# Radio-86RK-SRAM.net
KiCad netlist of a schematic drawn in EAGLE
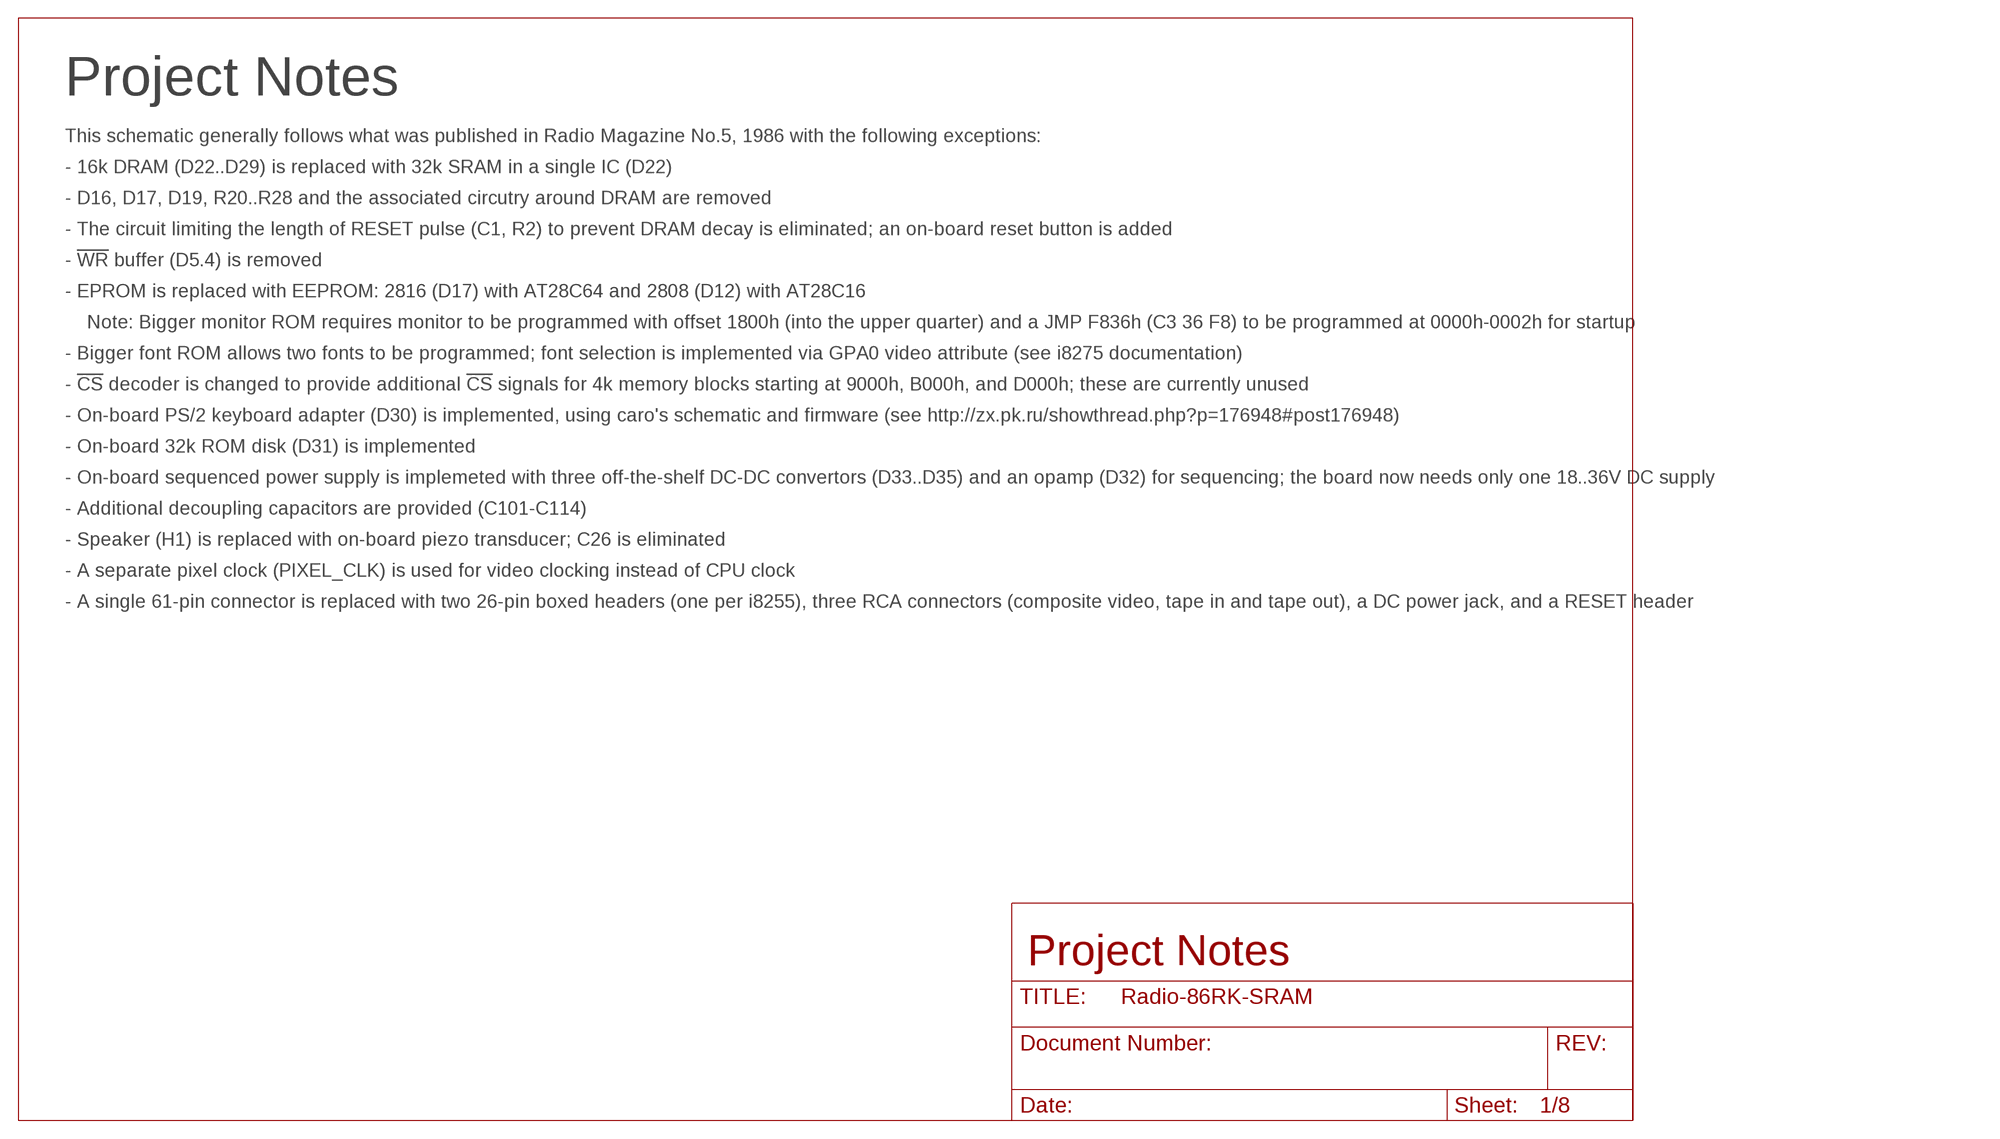
[diagram p0: schematic, sheet 1]
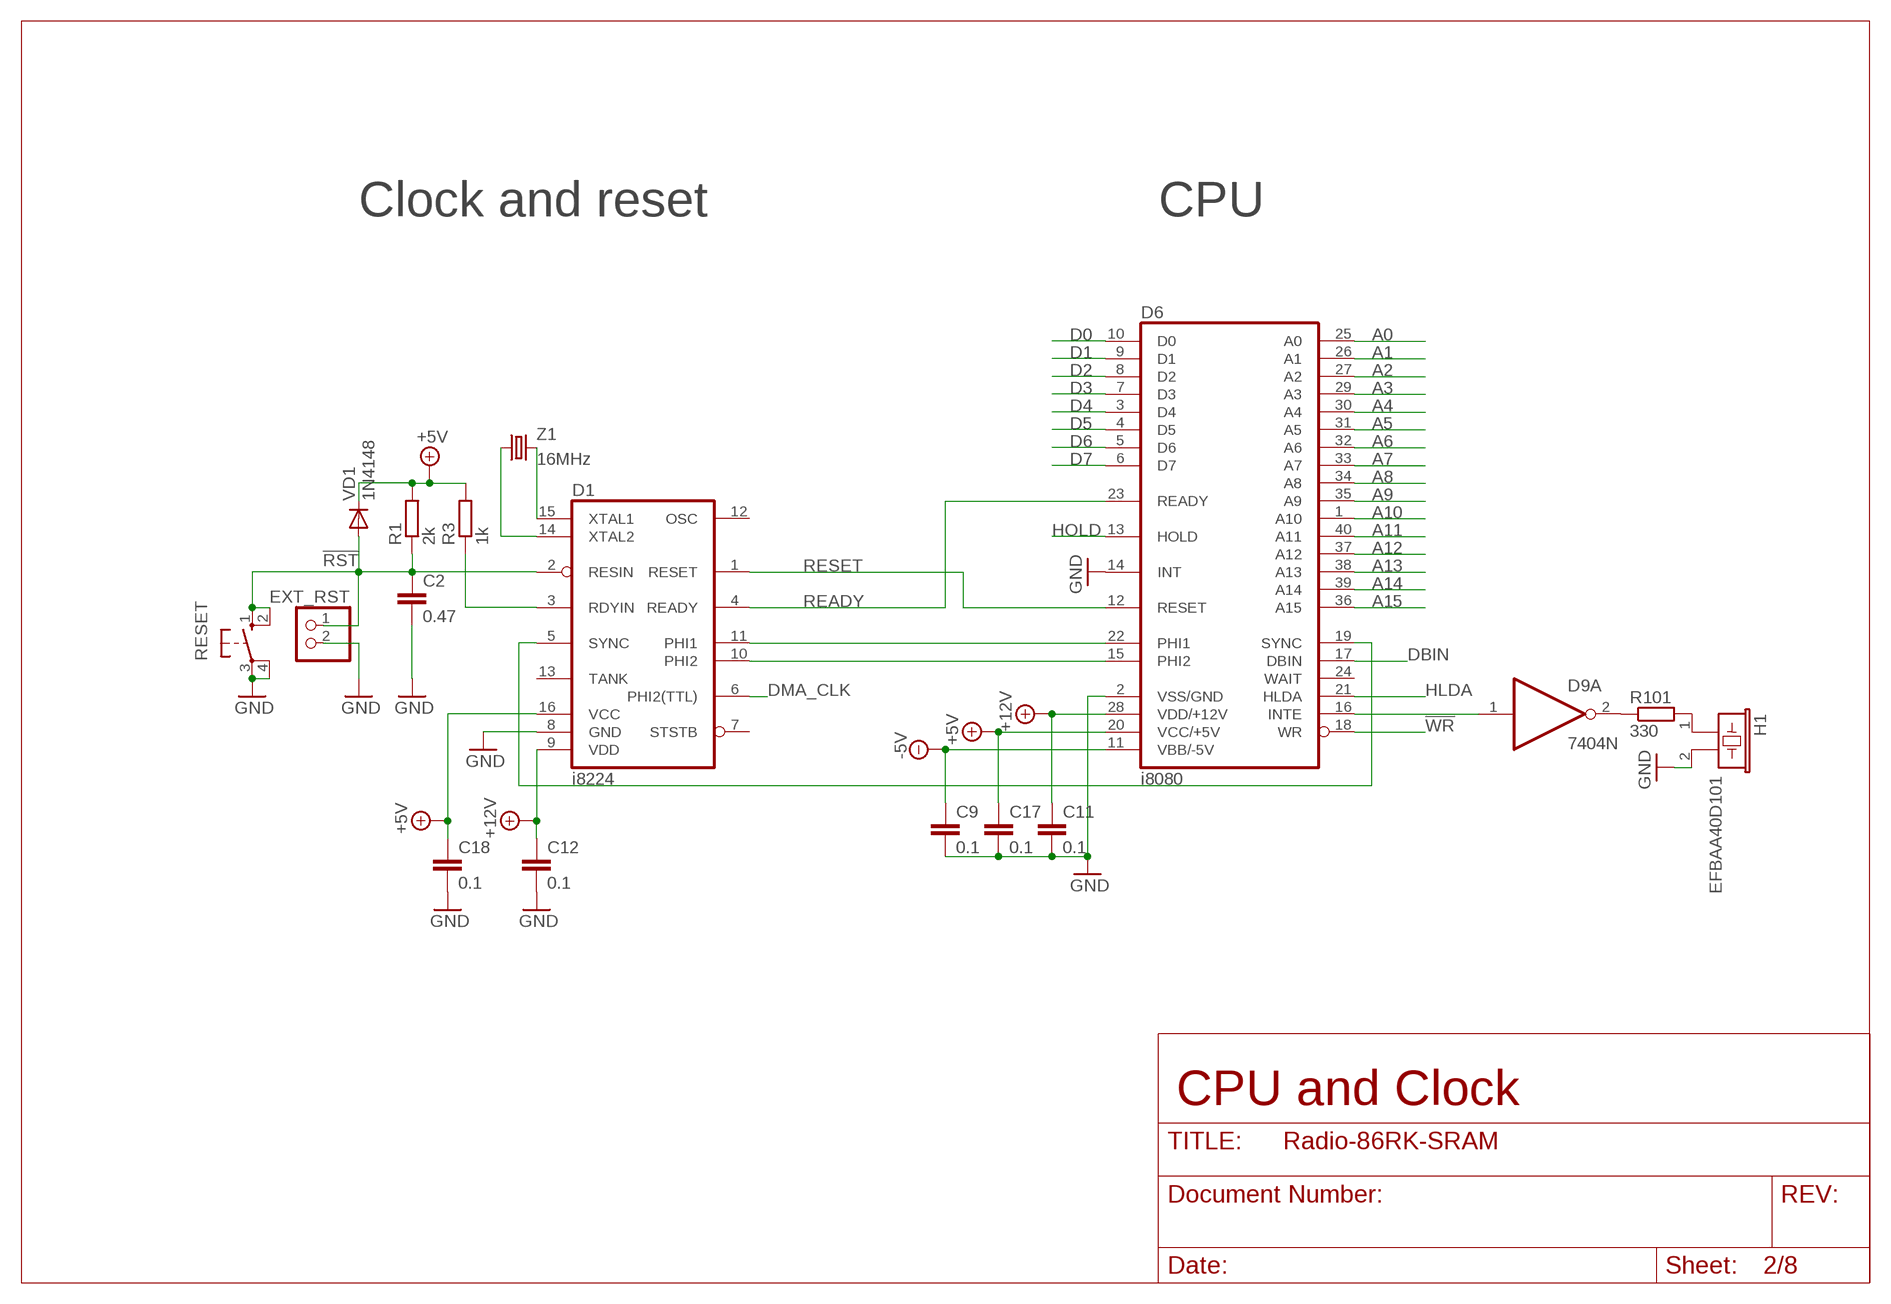
[diagram p1: schematic, sheet 2]
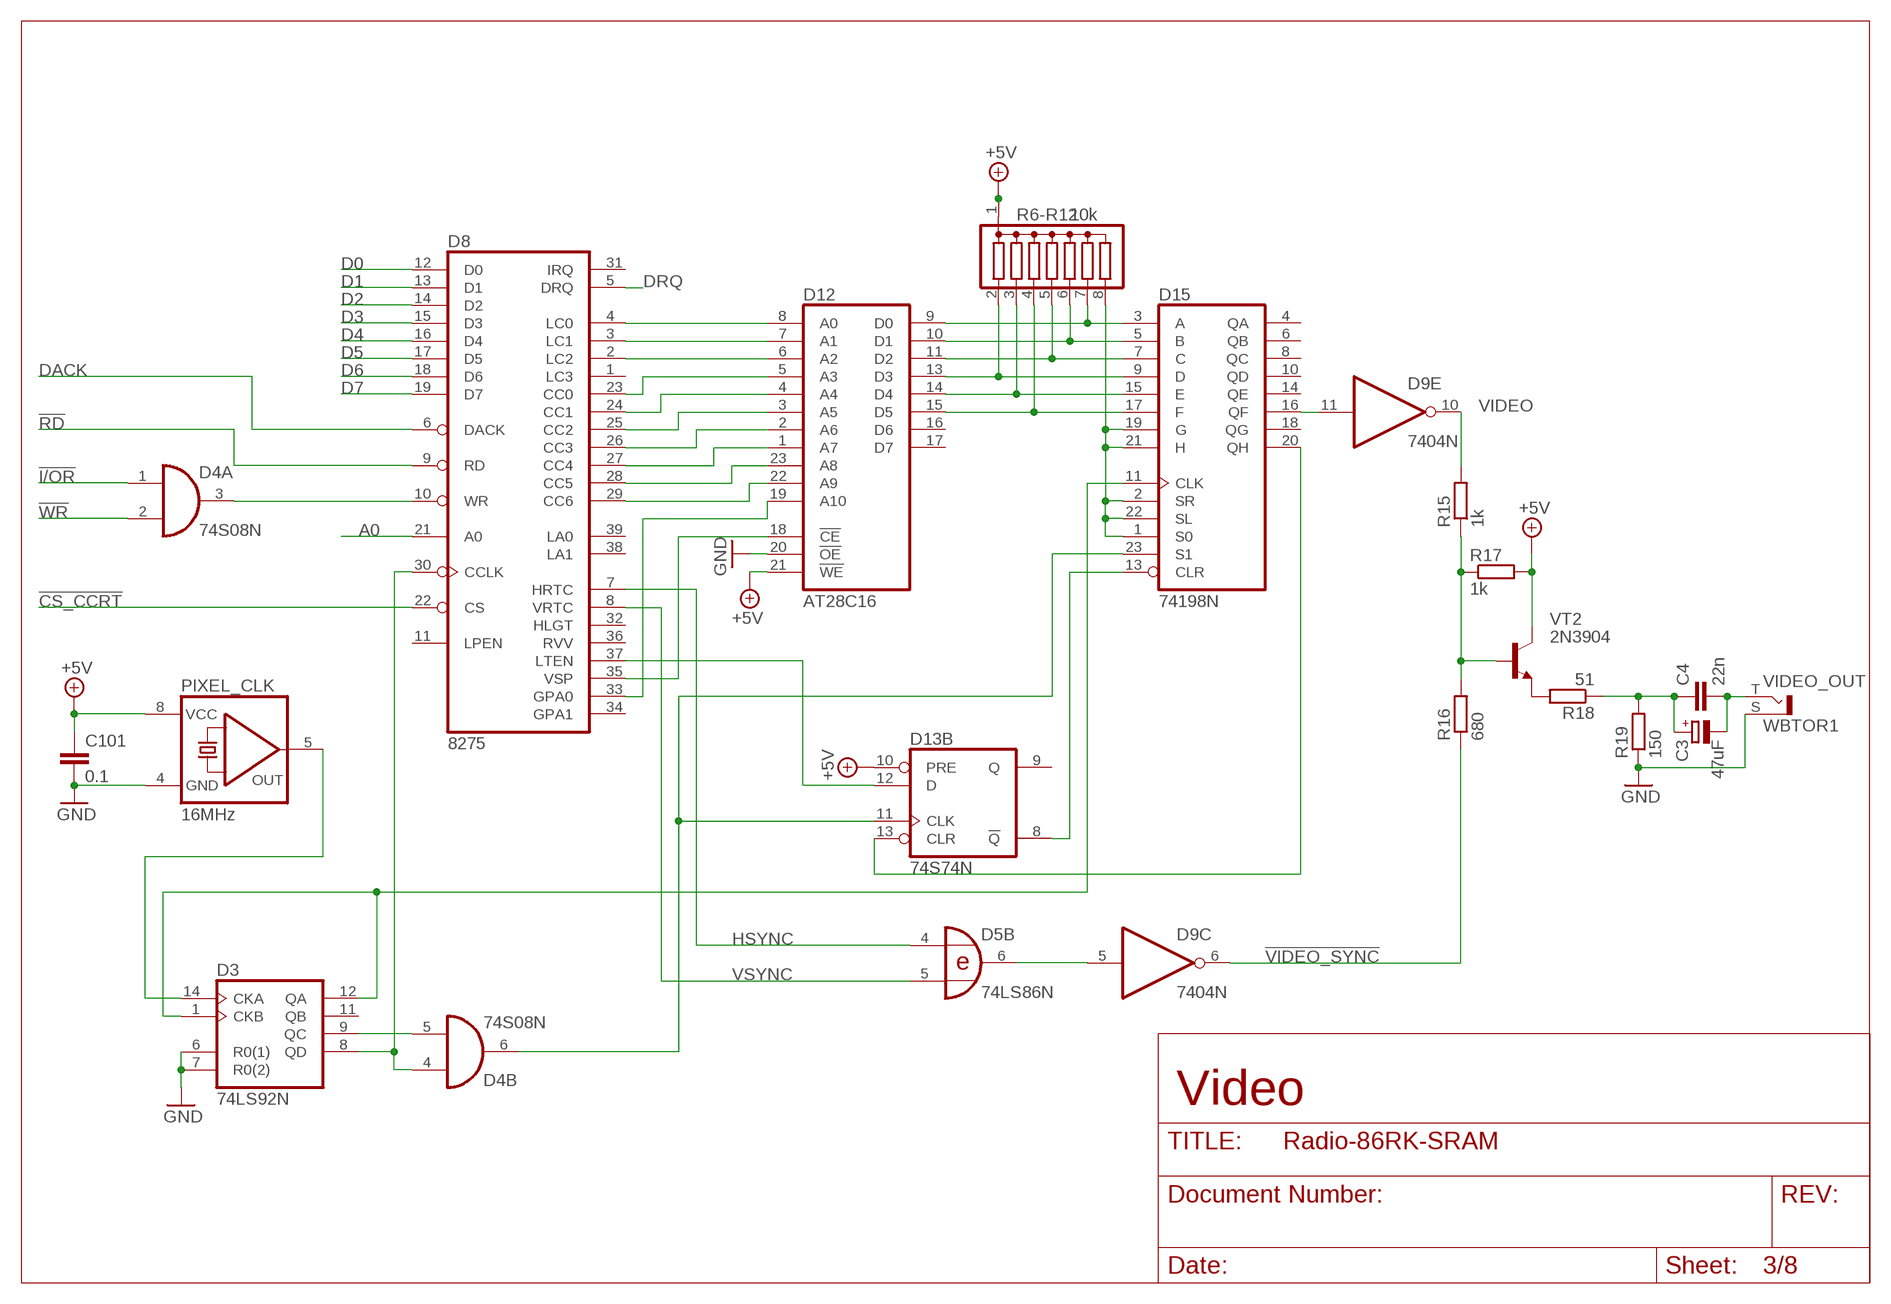
[diagram p2: schematic, sheet 3]
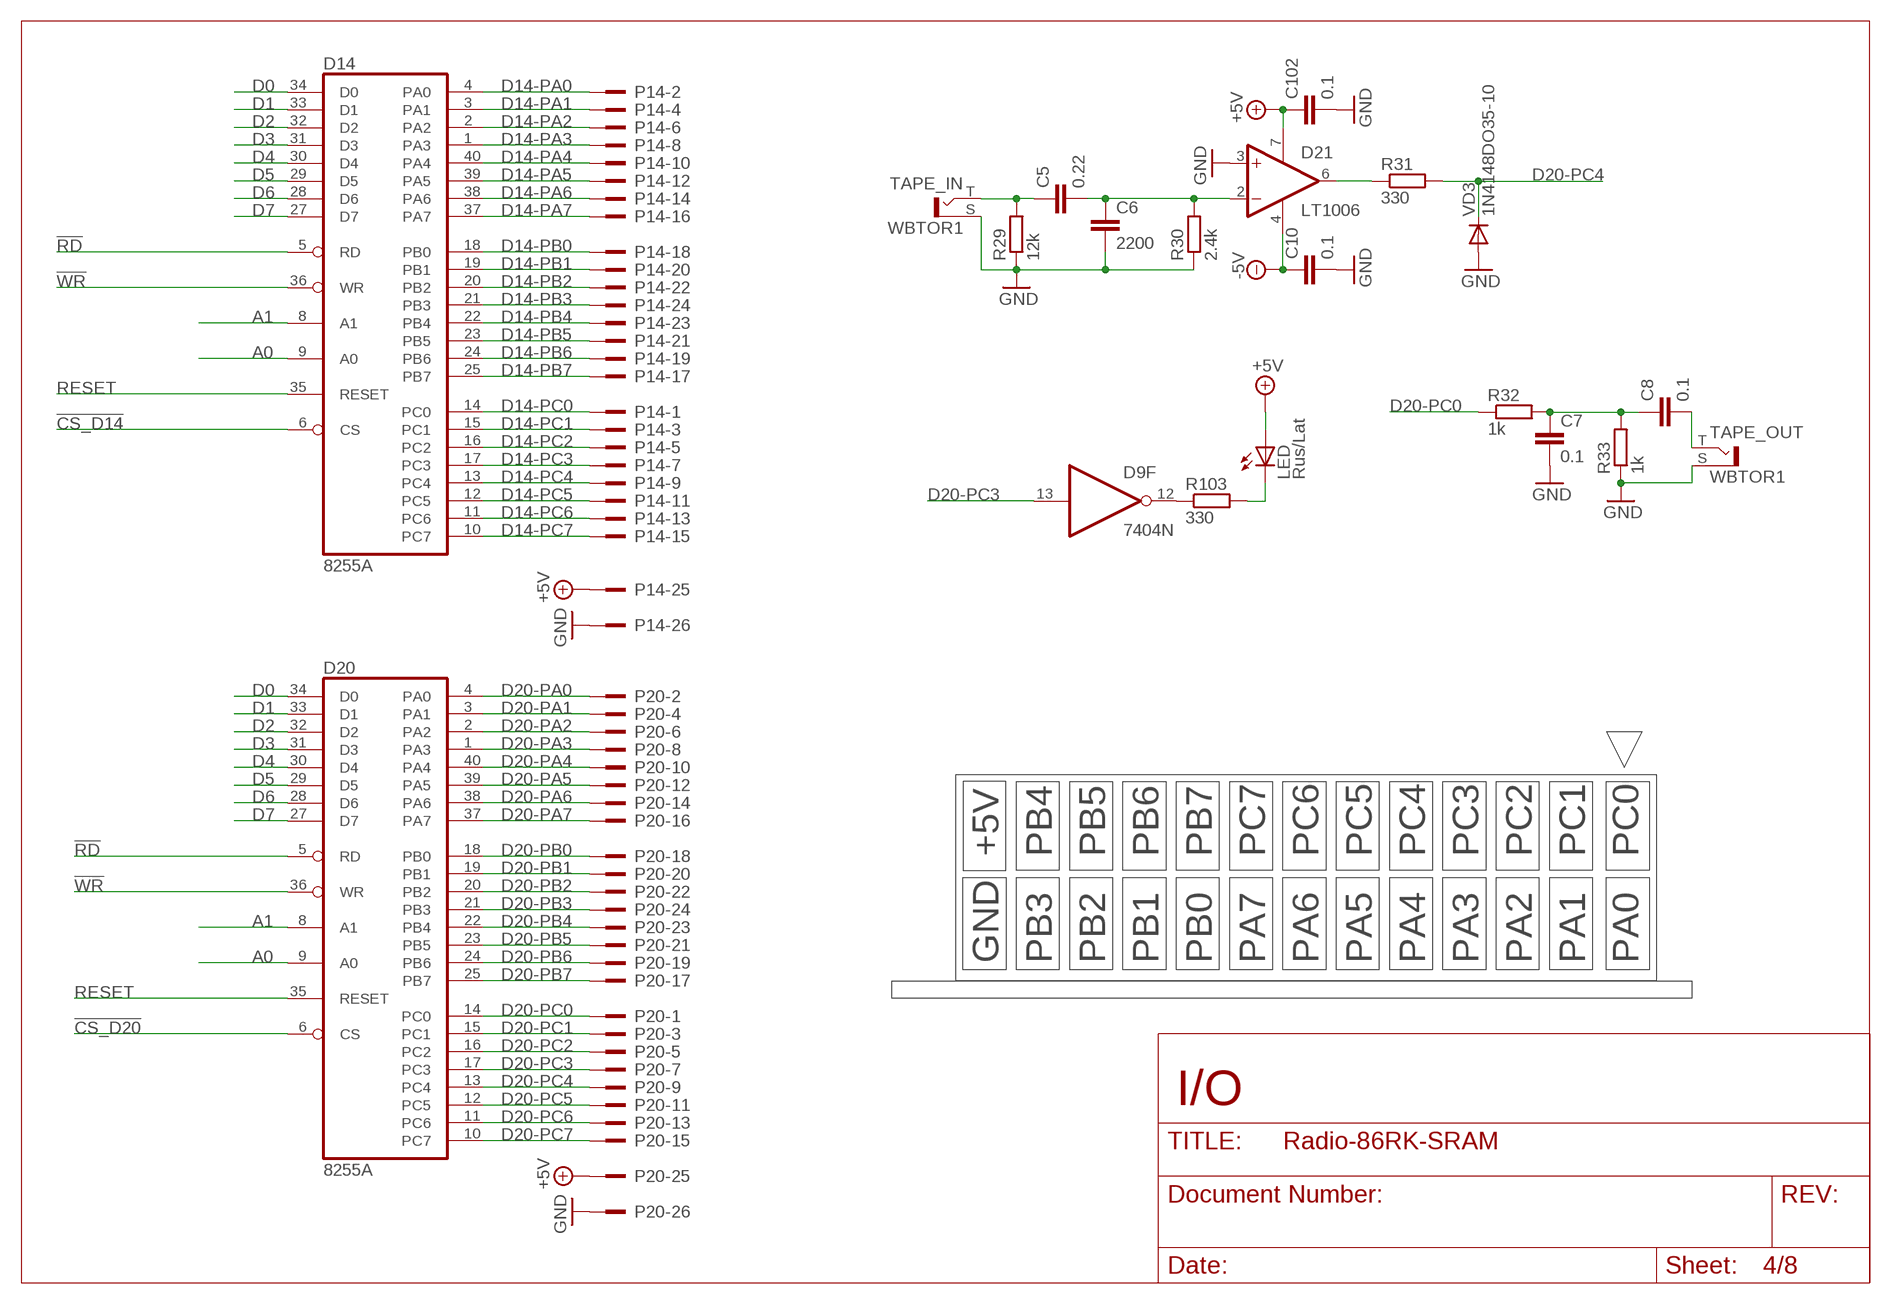
[diagram p3: schematic, sheet 4]
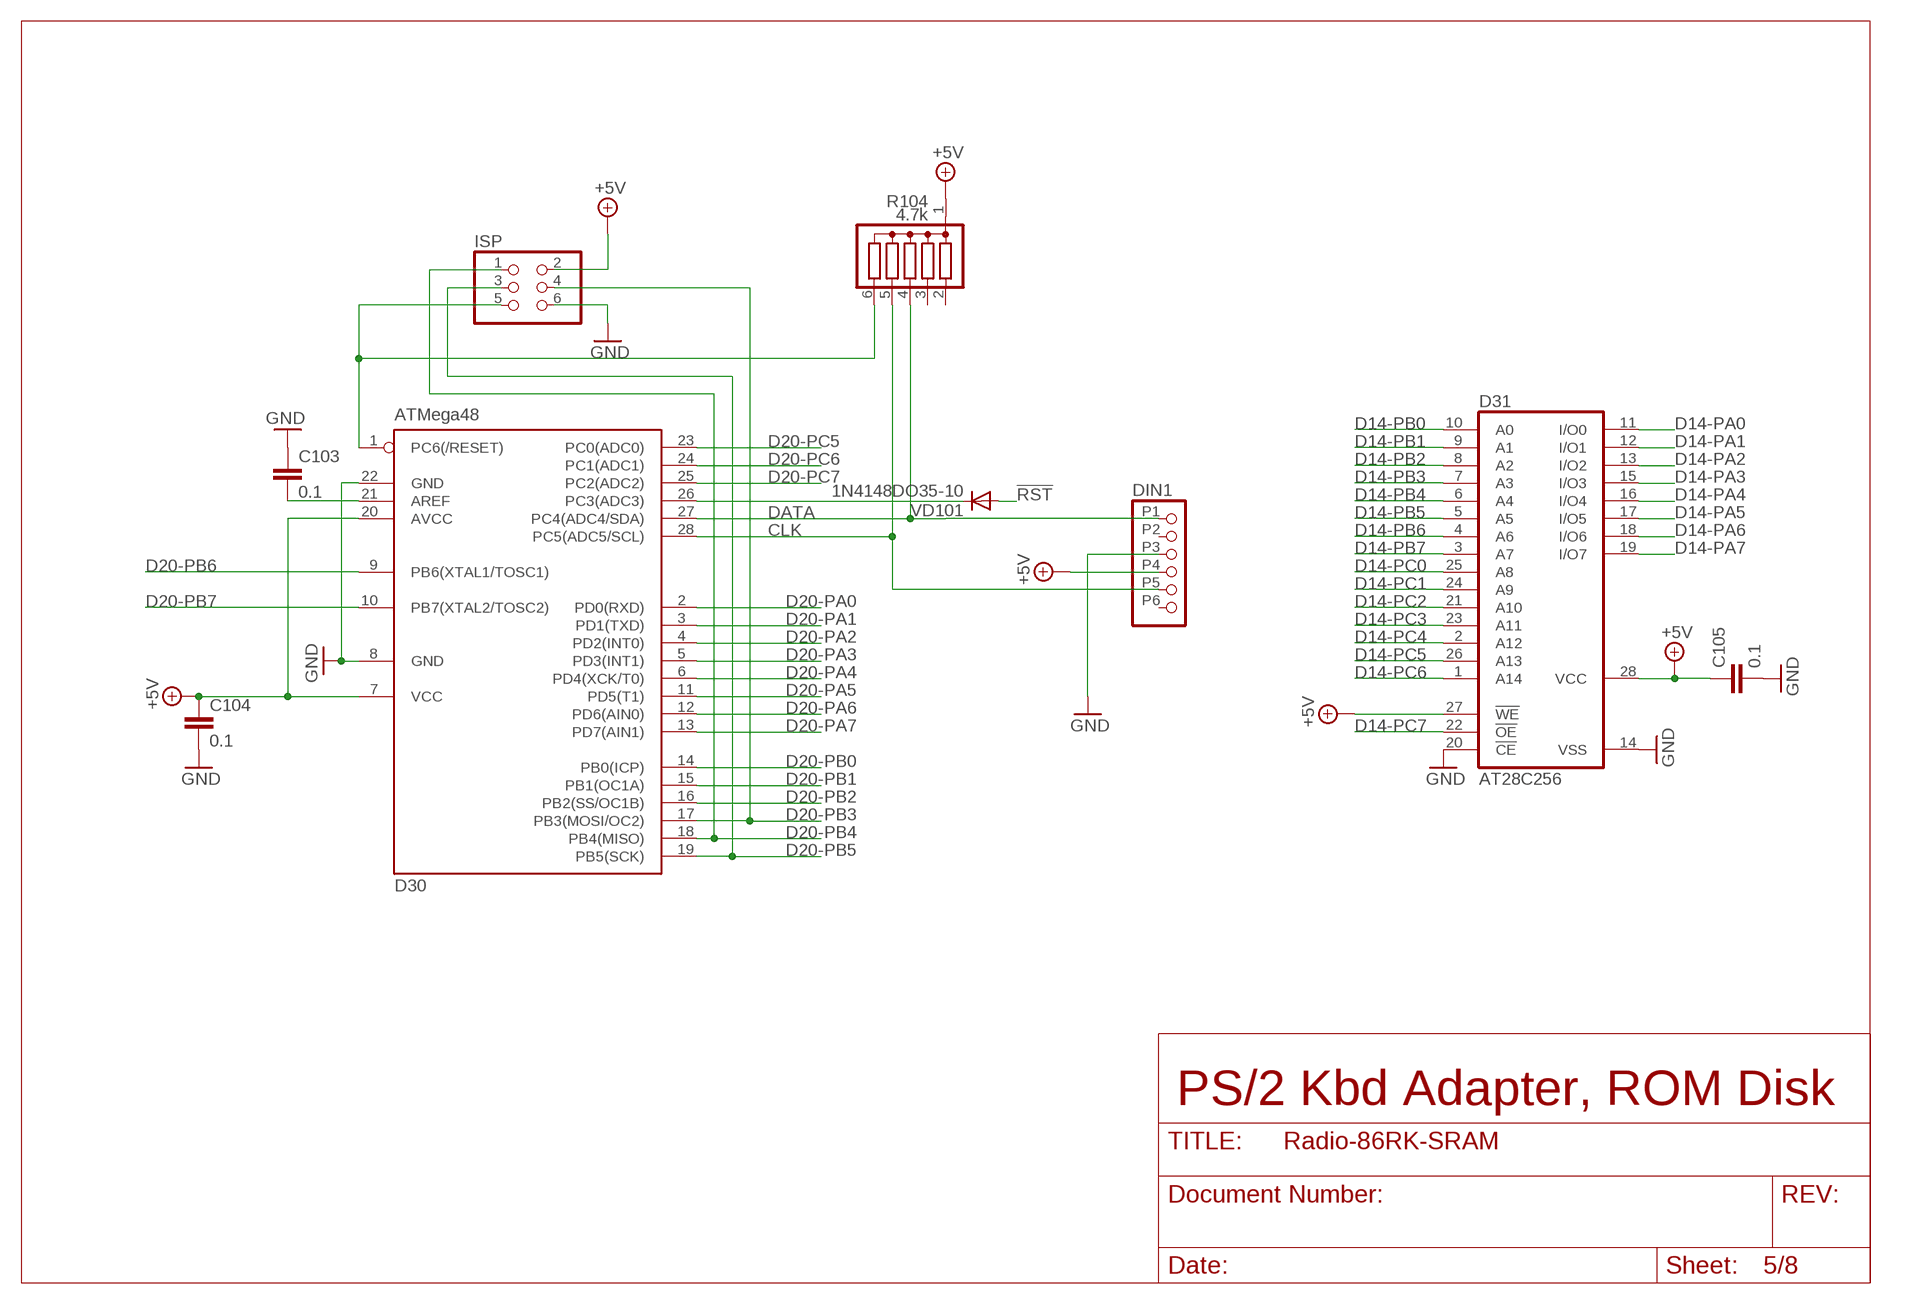
[diagram p4: schematic, sheet 5]
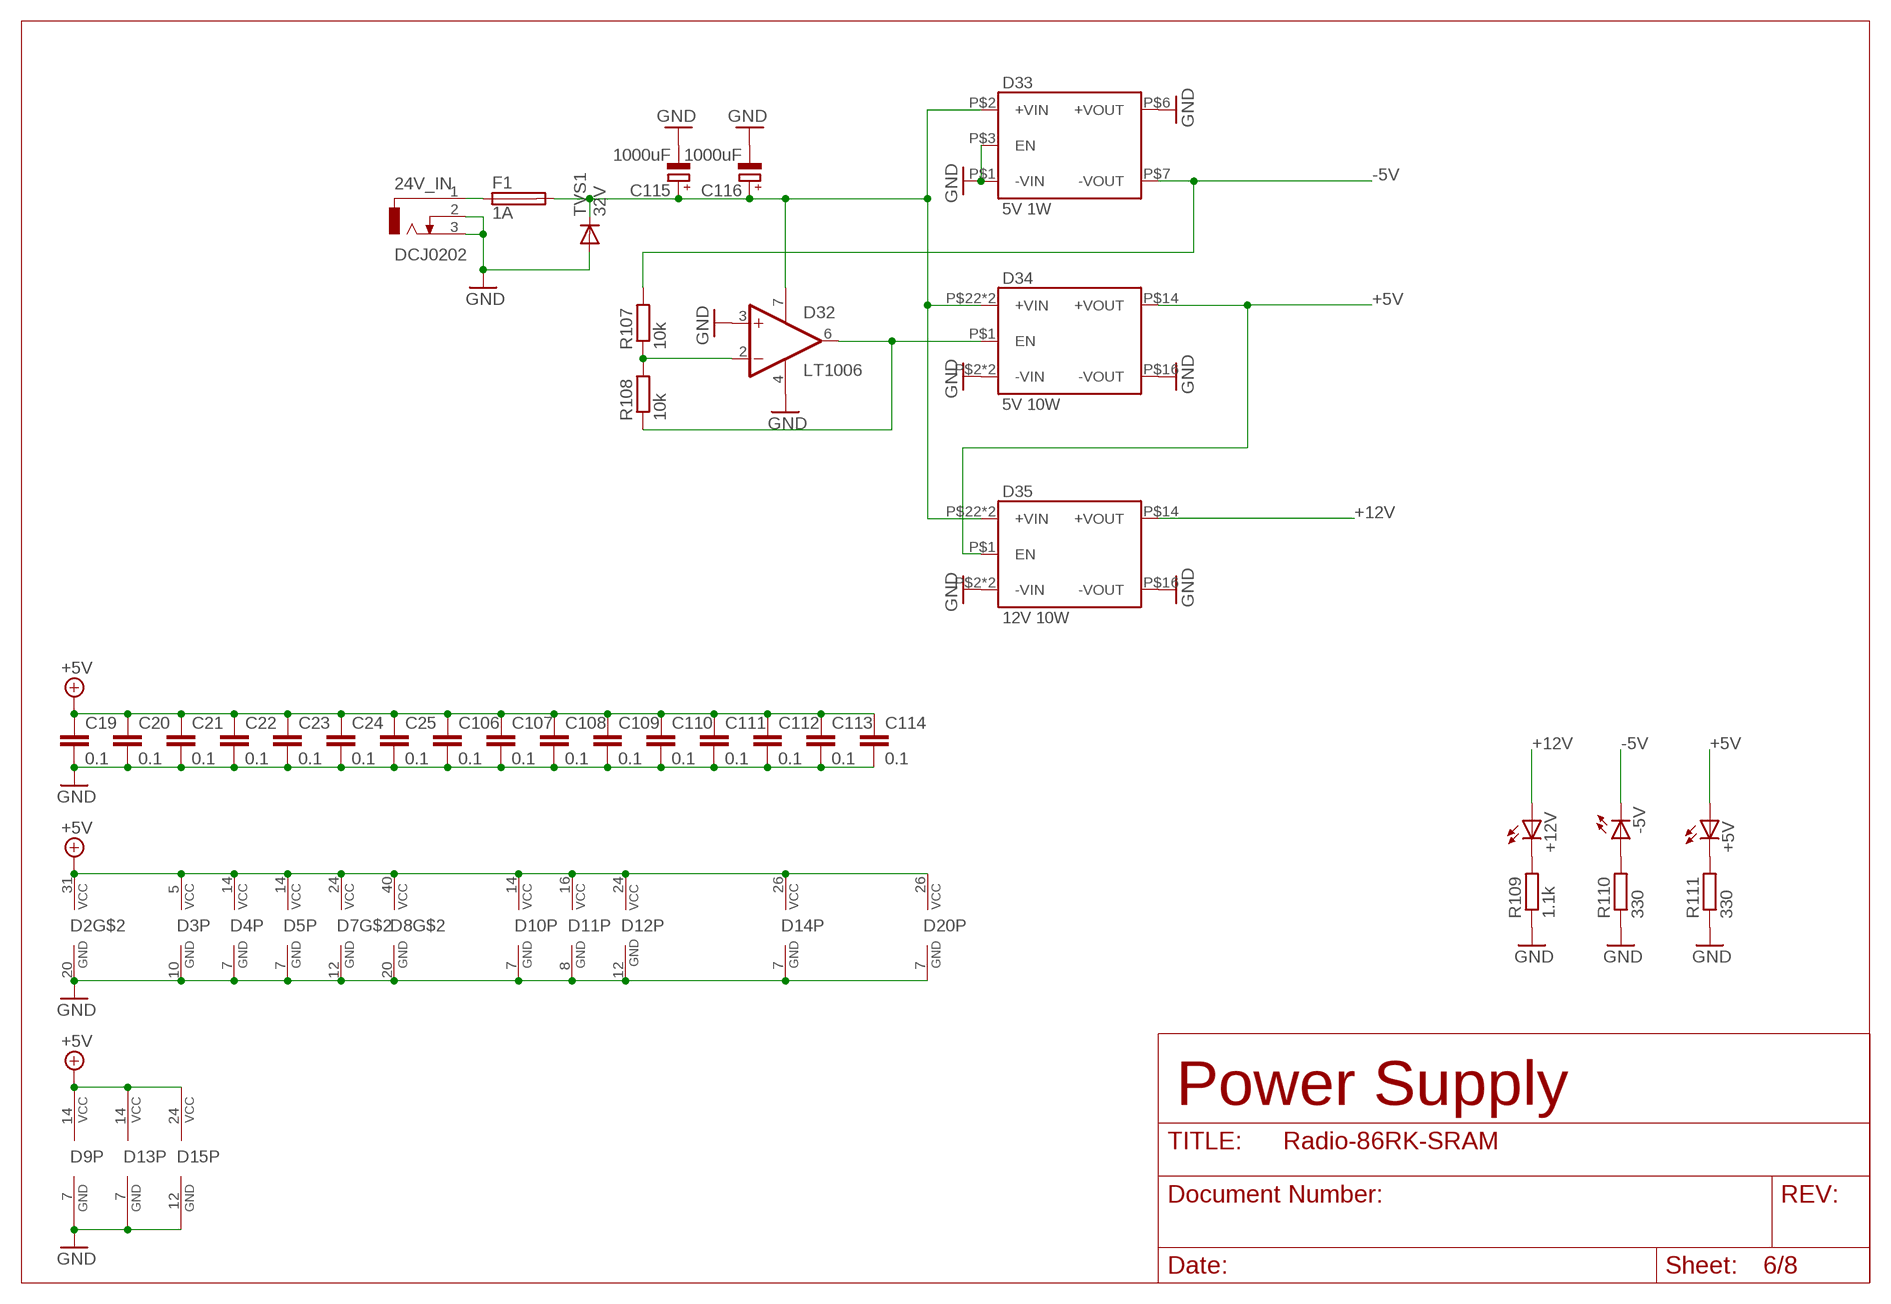
[diagram p5: schematic, sheet 6]
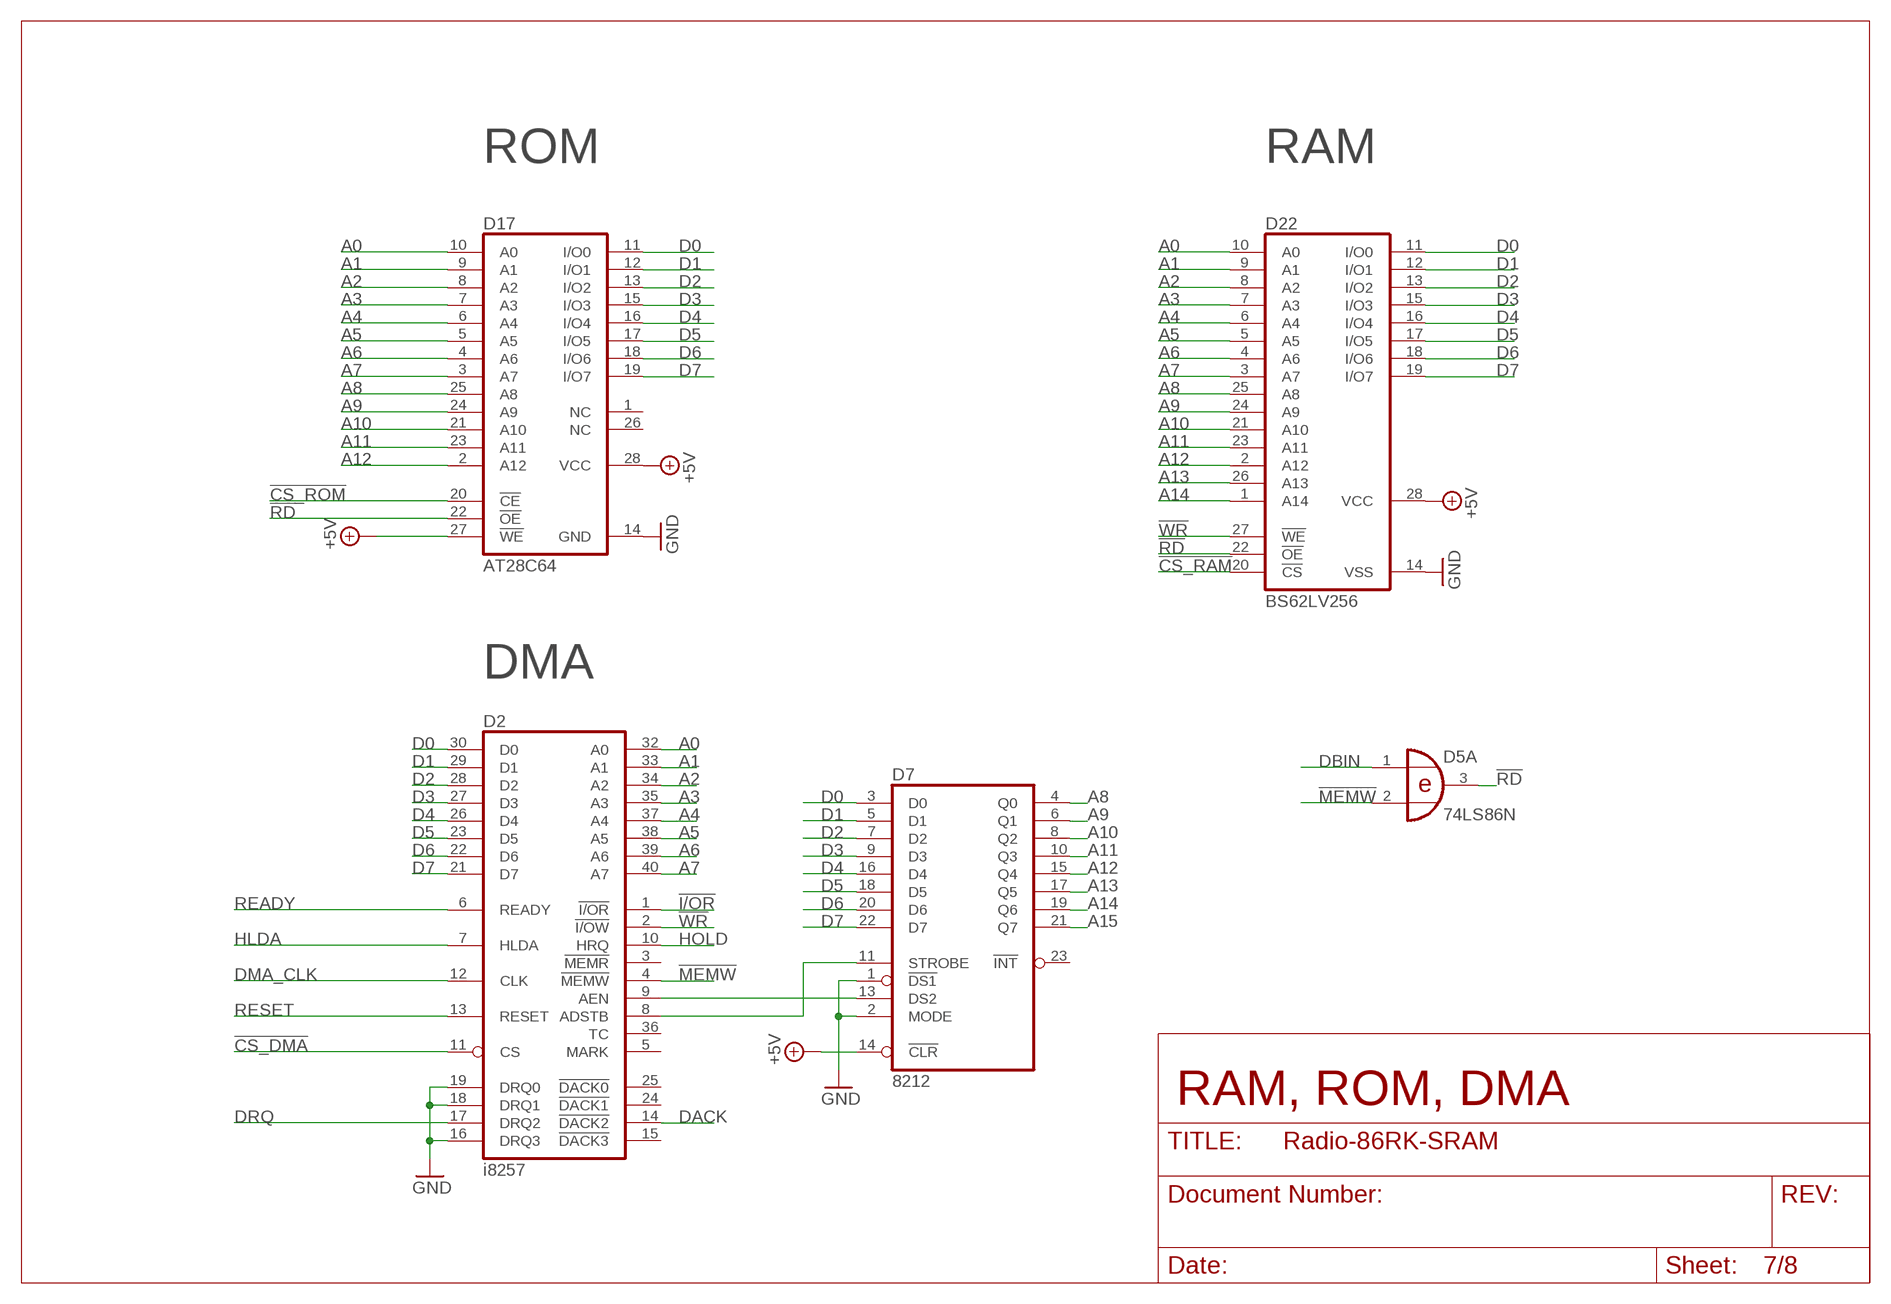
[diagram p6: schematic, sheet 7]
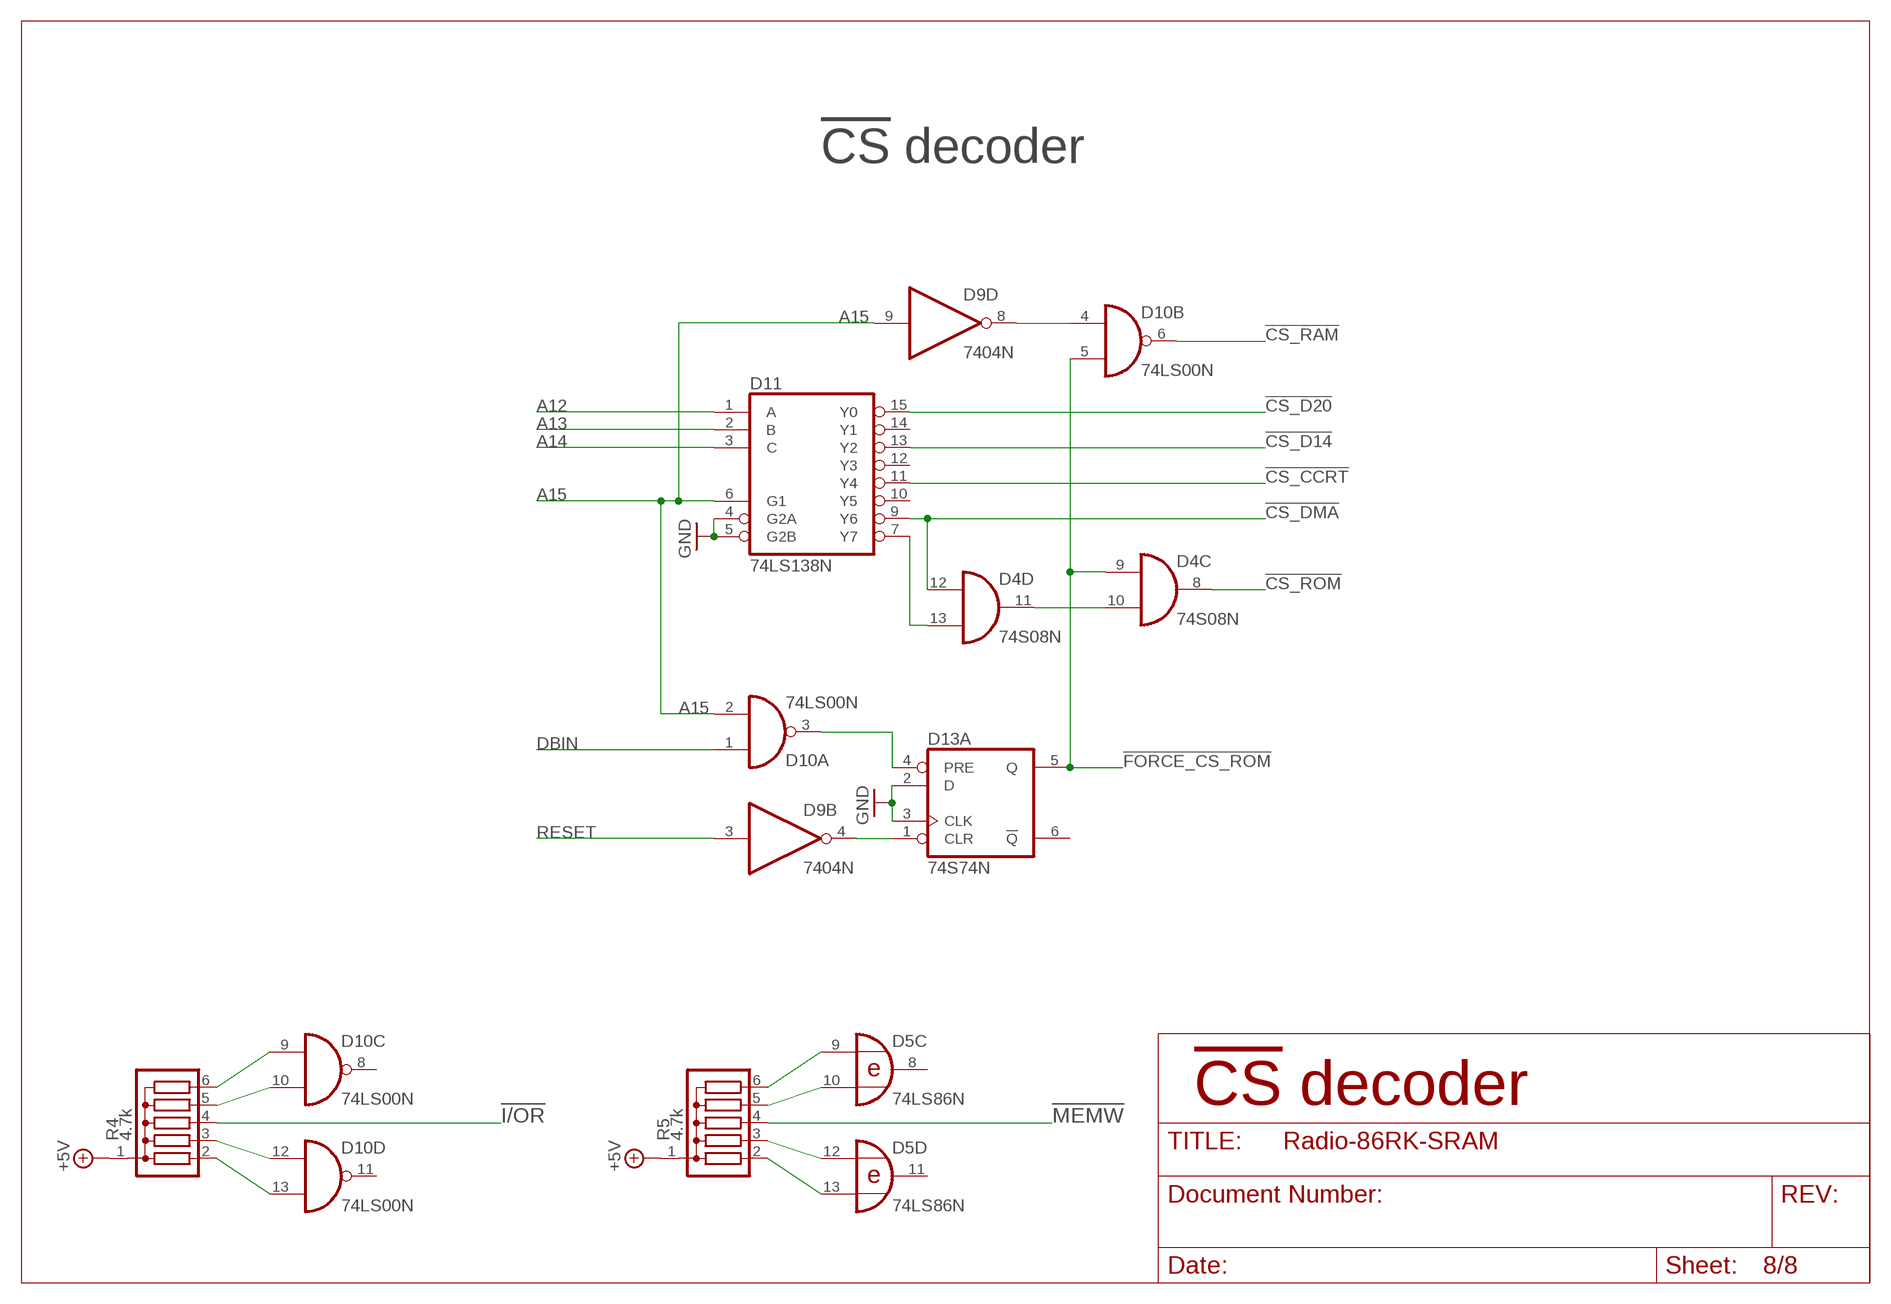
[diagram p7: schematic, sheet 8]

(export (version "E")
  (design (tool "Eeschema 10.0.6"))
  (components
    (comp (ref "C103")
      (value "0.1")
      (footprint "eagle-import:C050-024X044")
      (libsource (lib "eagle-import") (part "C-EU050-024X044"))
    )
    (comp (ref "C104")
      (value "0.1")
      (footprint "eagle-import:C050-024X044")
      (libsource (lib "eagle-import") (part "C-EU050-024X044"))
    )
    (comp (ref "C105")
      (value "0.1")
      (footprint "eagle-import:C050-024X044")
      (libsource (lib "eagle-import") (part "C-EU050-024X044"))
    )
    (comp (ref "D30")
      (value "ATMega48")
      (footprint "eagle-import:DIL28-3")
      (libsource (lib "eagle-import") (part "MEGA8-P"))
    )
    (comp (ref "D31")
      (value "AT28C256")
      (footprint "eagle-import:DIL28-6")
      (fields (field (name "MPN") "HN58C256AP85E"))
      (libsource (lib "eagle-import") (part "58C256P"))
    )
    (comp (ref "DIN1")
      (value "TM0508A/6")
      (footprint "eagle-import:MINI-DIN6")
      (libsource (lib "eagle-import") (part "TM0508A/6"))
    )
    (comp (ref "ISP")
      (value "PINHD-2X3")
      (footprint "eagle-import:2X03")
      (libsource (lib "eagle-import") (part "PINHD-2X3"))
    )
    (comp (ref "R104")
      (value "4.7k")
      (footprint "eagle-import:SIL6")
      (libsource (lib "eagle-import") (part "G05R"))
    )
    (comp (ref "VD101")
      (value "1N4148DO35-10")
      (footprint "eagle-import:DO35-10")
      (libsource (lib "eagle-import") (part "1N4148DO35-10"))
    )
    (comp (ref "D2")
      (value "i8257")
      (footprint "eagle-import:DIL40")
      (libsource (lib "eagle-import") (part "8257"))
    )
    (comp (ref "D5")
      (value "74LS86N")
      (footprint "eagle-import:DIL14")
      (libsource (lib "eagle-import") (part "7486NAC"))
    )
    (comp (ref "D7")
      (value "8212")
      (footprint "eagle-import:DIL24-6")
      (libsource (lib "eagle-import") (part "8212"))
    )
    (comp (ref "D17")
      (value "AT28C64")
      (footprint "eagle-import:DIL28-6")
      (fields (field (name "MPN") "AT28C64B-15PU"))
      (libsource (lib "eagle-import") (part "28C64C"))
    )
    (comp (ref "D22")
      (value "BS62LV256")
      (footprint "eagle-import:DIL28-6")
      (libsource (lib "eagle-import") (part "62256P"))
    )
    (comp (ref "D4")
      (value "74S08N")
      (footprint "eagle-import:DIL14")
      (libsource (lib "eagle-import") (part "7408NS"))
    )
    (comp (ref "D9")
      (value "7404N")
      (footprint "eagle-import:DIL14")
      (libsource (lib "eagle-import") (part "7404N"))
    )
    (comp (ref "D10")
      (value "74LS00N")
      (footprint "eagle-import:DIL14")
      (libsource (lib "eagle-import") (part "7400NHC"))
    )
    (comp (ref "D11")
      (value "74LS138N")
      (footprint "eagle-import:DIL16")
      (libsource (lib "eagle-import") (part "74138NLS"))
    )
    (comp (ref "D13")
      (value "74S74N")
      (footprint "eagle-import:DIL14")
      (libsource (lib "eagle-import") (part "7474NS"))
    )
    (comp (ref "R4")
      (value "4.7k")
      (footprint "eagle-import:SIL6")
      (libsource (lib "eagle-import") (part "G05R"))
    )
    (comp (ref "R5")
      (value "4.7k")
      (footprint "eagle-import:SIL6")
      (libsource (lib "eagle-import") (part "G05R"))
    )
    (comp (ref "+5V")
      (value "LED3MM")
      (footprint "eagle-import:LED3MM")
      (libsource (lib "eagle-import") (part "LED3MM"))
    )
    (comp (ref "+12V")
      (value "LED3MM")
      (footprint "eagle-import:LED3MM")
      (libsource (lib "eagle-import") (part "LED3MM"))
    )
    (comp (ref "-5V")
      (value "LED3MM")
      (footprint "eagle-import:LED3MM")
      (libsource (lib "eagle-import") (part "LED3MM"))
    )
    (comp (ref "24V_IN")
      (value "DCJ0202")
      (footprint "eagle-import:DCJ0202")
      (libsource (lib "eagle-import") (part "DCJ0202"))
    )
    (comp (ref "C19")
      (value "0.1")
      (footprint "eagle-import:C050-024X044")
      (libsource (lib "eagle-import") (part "C-EU050-024X044"))
    )
    (comp (ref "C20")
      (value "0.1")
      (footprint "eagle-import:C050-024X044")
      (libsource (lib "eagle-import") (part "C-EU050-024X044"))
    )
    (comp (ref "C21")
      (value "0.1")
      (footprint "eagle-import:C050-024X044")
      (libsource (lib "eagle-import") (part "C-EU050-024X044"))
    )
    (comp (ref "C22")
      (value "0.1")
      (footprint "eagle-import:C050-024X044")
      (libsource (lib "eagle-import") (part "C-EU050-024X044"))
    )
    (comp (ref "C23")
      (value "0.1")
      (footprint "eagle-import:C050-024X044")
      (libsource (lib "eagle-import") (part "C-EU050-024X044"))
    )
    (comp (ref "C24")
      (value "0.1")
      (footprint "eagle-import:C050-024X044")
      (libsource (lib "eagle-import") (part "C-EU050-024X044"))
    )
    (comp (ref "C25")
      (value "0.1")
      (footprint "eagle-import:C050-024X044")
      (libsource (lib "eagle-import") (part "C-EU050-024X044"))
    )
    (comp (ref "C106")
      (value "0.1")
      (footprint "eagle-import:C050-024X044")
      (libsource (lib "eagle-import") (part "C-EU050-024X044"))
    )
    (comp (ref "C107")
      (value "0.1")
      (footprint "eagle-import:C050-024X044")
      (libsource (lib "eagle-import") (part "C-EU050-024X044"))
    )
    (comp (ref "C108")
      (value "0.1")
      (footprint "eagle-import:C050-024X044")
      (libsource (lib "eagle-import") (part "C-EU050-024X044"))
    )
    (comp (ref "C109")
      (value "0.1")
      (footprint "eagle-import:C050-024X044")
      (libsource (lib "eagle-import") (part "C-EU050-024X044"))
    )
    (comp (ref "C110")
      (value "0.1")
      (footprint "eagle-import:C050-024X044")
      (libsource (lib "eagle-import") (part "C-EU050-024X044"))
    )
    (comp (ref "C111")
      (value "0.1")
      (footprint "eagle-import:C050-024X044")
      (libsource (lib "eagle-import") (part "C-EU050-024X044"))
    )
    (comp (ref "C112")
      (value "0.1")
      (footprint "eagle-import:C050-024X044")
      (libsource (lib "eagle-import") (part "C-EU050-024X044"))
    )
    (comp (ref "C113")
      (value "0.1")
      (footprint "eagle-import:C050-024X044")
      (libsource (lib "eagle-import") (part "C-EU050-024X044"))
    )
    (comp (ref "C114")
      (value "0.1")
      (footprint "eagle-import:C050-024X044")
      (libsource (lib "eagle-import") (part "C-EU050-024X044"))
    )
    (comp (ref "C115")
      (value "1000uF")
      (footprint "eagle-import:E5-13")
      (libsource (lib "eagle-import") (part "CPOL-EUE5-13"))
    )
    (comp (ref "C116")
      (value "1000uF")
      (footprint "eagle-import:E7,5-18")
      (libsource (lib "eagle-import") (part "CPOL-EUE7.5-18"))
    )
    (comp (ref "D3")
      (value "74LS92N")
      (footprint "eagle-import:DIL14")
      (libsource (lib "eagle-import") (part "7492NLS"))
    )
    (comp (ref "D8")
      (value "8275")
      (footprint "eagle-import:DIL40")
      (libsource (lib "eagle-import") (part "8275"))
    )
    (comp (ref "D12")
      (value "AT28C16")
      (footprint "eagle-import:DIL24")
      (libsource (lib "eagle-import") (part "2816"))
    )
    (comp (ref "D14")
      (value "8255A")
      (footprint "eagle-import:DIL40")
      (libsource (lib "eagle-import") (part "8255A"))
    )
    (comp (ref "D15")
      (value "74198N")
      (footprint "eagle-import:DIL24-6")
      (libsource (lib "eagle-import") (part "74198N"))
    )
    (comp (ref "D20")
      (value "8255A")
      (footprint "eagle-import:DIL40")
      (libsource (lib "eagle-import") (part "8255A"))
    )
    (comp (ref "D32")
      (value "LT1006")
      (footprint "eagle-import:DIL08")
      (libsource (lib "eagle-import") (part "1AMP_P7+4N"))
    )
    (comp (ref "D33")
      (value "5V 1W")
      (footprint "eagle-import:DC_DC_SIP")
      (libsource (lib "eagle-import") (part "IW_S"))
    )
    (comp (ref "D34")
      (value "5V 10W")
      (footprint "eagle-import:DC_DC_24PIN")
      (libsource (lib "eagle-import") (part "JTF_S"))
    )
    (comp (ref "D35")
      (value "12V 10W")
      (footprint "eagle-import:DC_DC_24PIN")
      (libsource (lib "eagle-import") (part "JTF_S"))
    )
    (comp (ref "F1")
      (value "1A")
      (footprint "eagle-import:TE5")
      (libsource (lib "eagle-import") (part "TE5"))
    )
    (comp (ref "R107")
      (value "10k")
      (footprint "eagle-import:0207_10")
      (libsource (lib "eagle-import") (part "R-EU_0207/10"))
    )
    (comp (ref "R108")
      (value "10k")
      (footprint "eagle-import:0207_10")
      (libsource (lib "eagle-import") (part "R-EU_0207/10"))
    )
    (comp (ref "R109")
      (value "1.1k")
      (footprint "eagle-import:0207_10")
      (libsource (lib "eagle-import") (part "R-EU_0207/10"))
    )
    (comp (ref "R110")
      (value "330")
      (footprint "eagle-import:0207_10")
      (libsource (lib "eagle-import") (part "R-EU_0207/10"))
    )
    (comp (ref "R111")
      (value "330")
      (footprint "eagle-import:0207_10")
      (libsource (lib "eagle-import") (part "R-EU_0207/10"))
    )
    (comp (ref "TVS1")
      (value "32V")
      (footprint "eagle-import:DO41-10")
      (libsource (lib "eagle-import") (part "DIODE-DO41-10"))
    )
    (comp (ref "C5")
      (value "0.22")
      (footprint "eagle-import:C050-024X044")
      (libsource (lib "eagle-import") (part "C-EU050-024X044"))
    )
    (comp (ref "C6")
      (value "2200")
      (footprint "eagle-import:C050-024X044")
      (libsource (lib "eagle-import") (part "C-EU050-024X044"))
    )
    (comp (ref "C7")
      (value "0.1")
      (footprint "eagle-import:C050-024X044")
      (libsource (lib "eagle-import") (part "C-EU050-024X044"))
    )
    (comp (ref "C8")
      (value "0.1")
      (footprint "eagle-import:C050-024X044")
      (libsource (lib "eagle-import") (part "C-EU050-024X044"))
    )
    (comp (ref "C10")
      (value "0.1")
      (footprint "eagle-import:C050-024X044")
      (libsource (lib "eagle-import") (part "C-EU050-024X044"))
    )
    (comp (ref "C102")
      (value "0.1")
      (footprint "eagle-import:C050-024X044")
      (libsource (lib "eagle-import") (part "C-EU050-024X044"))
    )
    (comp (ref "D21")
      (value "LT1006")
      (footprint "eagle-import:DIL08")
      (libsource (lib "eagle-import") (part "1AMP_P7+4N"))
    )
    (comp (ref "LED")
      (value "Rus/Lat")
      (footprint "eagle-import:LED3MM")
      (libsource (lib "eagle-import") (part "LED3MM"))
    )
    (comp (ref "P14")
      (value "2526-5")
      (footprint "eagle-import:PAK100_2500-5-26")
      (fields (field (name "OC_FARNELL") "9838392"))
      (libsource (lib "eagle-import") (part "2526-5"))
    )
    (comp (ref "P20")
      (value "2526-5")
      (footprint "eagle-import:PAK100_2500-5-26")
      (fields (field (name "OC_FARNELL") "9838392"))
      (libsource (lib "eagle-import") (part "2526-5"))
    )
    (comp (ref "R29")
      (value "12k")
      (footprint "eagle-import:0207_10")
      (libsource (lib "eagle-import") (part "R-EU_0207/10"))
    )
    (comp (ref "R30")
      (value "2.4k")
      (footprint "eagle-import:0207_10")
      (libsource (lib "eagle-import") (part "R-EU_0207/10"))
    )
    (comp (ref "R31")
      (value "330")
      (footprint "eagle-import:0207_10")
      (libsource (lib "eagle-import") (part "R-EU_0207/10"))
    )
    (comp (ref "R32")
      (value "1k")
      (footprint "eagle-import:0207_10")
      (libsource (lib "eagle-import") (part "R-EU_0207/10"))
    )
    (comp (ref "R33")
      (value "1k")
      (footprint "eagle-import:0207_10")
      (libsource (lib "eagle-import") (part "R-EU_0207/10"))
    )
    (comp (ref "R103")
      (value "330")
      (footprint "eagle-import:0207_10")
      (libsource (lib "eagle-import") (part "R-EU_0207/10"))
    )
    (comp (ref "TAPE_IN")
      (value "WBTOR1")
      (footprint "eagle-import:WBTOR1")
      (fields
        (field (name "MPN") "WBTOR 1 BLACK")
        (field (name "MPN_1") "WBTOR 1 BLACK")
        (field (name "OC_FARNELL") "1200146")
        (field (name "OC_NEWARK") "98K2588")
      )
      (libsource (lib "eagle-import") (part "WBTOR1"))
    )
    (comp (ref "TAPE_OUT")
      (value "WBTOR1")
      (footprint "eagle-import:WBTOR1")
      (fields
        (field (name "MPN") "WBTOR 1 BLACK")
        (field (name "MPN_1") "WBTOR 1 BLACK")
        (field (name "OC_FARNELL") "1200146")
        (field (name "OC_NEWARK") "98K2588")
      )
      (libsource (lib "eagle-import") (part "WBTOR1"))
    )
    (comp (ref "VD3")
      (value "1N4148DO35-10")
      (footprint "eagle-import:DO35-10")
      (libsource (lib "eagle-import") (part "1N4148DO35-10"))
    )
    (comp (ref "C3")
      (value "47uF")
      (footprint "eagle-import:E2,5-5")
      (libsource (lib "eagle-import") (part "CPOL-EUE2.5-5"))
    )
    (comp (ref "C4")
      (value "22n")
      (footprint "eagle-import:C050-024X044")
      (libsource (lib "eagle-import") (part "C-EU050-024X044"))
    )
    (comp (ref "C101")
      (value "0.1")
      (footprint "eagle-import:C050-024X044")
      (libsource (lib "eagle-import") (part "C-EU050-024X044"))
    )
    (comp (ref "PIXEL_CLK")
      (value "16MHz")
      (footprint "eagle-import:DIL08S")
      (libsource (lib "eagle-import") (part "QG5460"))
    )
    (comp (ref "R6-R12")
      (value "10k")
      (footprint "eagle-import:SIL8")
      (libsource (lib "eagle-import") (part "G07R"))
    )
    (comp (ref "R15")
      (value "1k")
      (footprint "eagle-import:0207_10")
      (libsource (lib "eagle-import") (part "R-EU_0207/10"))
    )
    (comp (ref "R16")
      (value "680")
      (footprint "eagle-import:0207_10")
      (libsource (lib "eagle-import") (part "R-EU_0207/10"))
    )
    (comp (ref "R17")
      (value "1k")
      (footprint "eagle-import:0207_10")
      (libsource (lib "eagle-import") (part "R-EU_0207/10"))
    )
    (comp (ref "R18")
      (value "51")
      (footprint "eagle-import:0207_10")
      (libsource (lib "eagle-import") (part "R-EU_0207/10"))
    )
    (comp (ref "R19")
      (value "150")
      (footprint "eagle-import:0207_10")
      (libsource (lib "eagle-import") (part "R-EU_0207/10"))
    )
    (comp (ref "VIDEO_OUT")
      (value "WBTOR1")
      (footprint "eagle-import:WBTOR1")
      (fields
        (field (name "MPN") "WBTOR 1 BLACK")
        (field (name "MPN_1") "WBTOR 1 BLACK")
        (field (name "OC_FARNELL") "1200146")
        (field (name "OC_NEWARK") "98K2588")
      )
      (libsource (lib "eagle-import") (part "WBTOR1"))
    )
    (comp (ref "VT2")
      (value "2N3904")
      (footprint "eagle-import:TO92")
      (libsource (lib "eagle-import") (part "2N3904"))
    )
    (comp (ref "C2")
      (value "0.47")
      (footprint "eagle-import:C050-024X044")
      (libsource (lib "eagle-import") (part "C-EU050-024X044"))
    )
    (comp (ref "C9")
      (value "0.1")
      (footprint "eagle-import:C050-024X044")
      (libsource (lib "eagle-import") (part "C-EU050-024X044"))
    )
    (comp (ref "C11")
      (value "0.1")
      (footprint "eagle-import:C050-024X044")
      (libsource (lib "eagle-import") (part "C-EU050-024X044"))
    )
    (comp (ref "C12")
      (value "0.1")
      (footprint "eagle-import:C050-024X044")
      (libsource (lib "eagle-import") (part "C-EU050-024X044"))
    )
    (comp (ref "C17")
      (value "0.1")
      (footprint "eagle-import:C050-024X044")
      (libsource (lib "eagle-import") (part "C-EU050-024X044"))
    )
    (comp (ref "C18")
      (value "0.1")
      (footprint "eagle-import:C050-024X044")
      (libsource (lib "eagle-import") (part "C-EU050-024X044"))
    )
    (comp (ref "D1")
      (value "i8224")
      (footprint "eagle-import:DIL16")
      (libsource (lib "eagle-import") (part "8224"))
    )
    (comp (ref "D6")
      (value "i8080")
      (footprint "eagle-import:DIL40")
      (libsource (lib "eagle-import") (part "8080"))
    )
    (comp (ref "EXT_RST")
      (value "PINHD-1X2")
      (footprint "eagle-import:1X02")
      (libsource (lib "eagle-import") (part "PINHD-1X2"))
    )
    (comp (ref "H1")
      (value "EFBAA40D101")
      (footprint "eagle-import:EFBAA40D101")
      (libsource (lib "eagle-import") (part "EFB?AA40D101"))
    )
    (comp (ref "R1")
      (value "2k")
      (footprint "eagle-import:0207_10")
      (libsource (lib "eagle-import") (part "R-EU_0207/10"))
    )
    (comp (ref "R3")
      (value "1k")
      (footprint "eagle-import:0207_10")
      (libsource (lib "eagle-import") (part "R-EU_0207/10"))
    )
    (comp (ref "R101")
      (value "330")
      (footprint "eagle-import:0207_10")
      (libsource (lib "eagle-import") (part "R-EU_0207/10"))
    )
    (comp (ref "RESET")
      (value "10-XX")
      (footprint "eagle-import:B3F-10XX")
      (fields (field (name "MPN") "B3F-1000"))
      (libsource (lib "eagle-import") (part "10-XX"))
    )
    (comp (ref "VD1")
      (value "1N4148")
      (footprint "eagle-import:DO35-10")
      (libsource (lib "eagle-import") (part "1N4148DO35-10"))
    )
    (comp (ref "Z1")
      (value "16MHz")
      (footprint "eagle-import:HC49U-V")
      (libsource (lib "eagle-import") (part "CRYSTALHC49U-V"))
    )
  )
  (nets
    (net (code "1") (name "+5V") (class "Default")
      (node (ref "+5V") (pin "A") (pinfunction "A_A") (pintype "passive"))
      (node (ref "C101") (pin "1") (pinfunction "1_1") (pintype "passive"))
      (node (ref "C102") (pin "1") (pinfunction "1_1") (pintype "passive"))
      (node (ref "C104") (pin "1") (pinfunction "1_1") (pintype "passive"))
      (node (ref "C105") (pin "1") (pinfunction "1_1") (pintype "passive"))
      (node (ref "C106") (pin "1") (pinfunction "1_1") (pintype "passive"))
      (node (ref "C107") (pin "1") (pinfunction "1_1") (pintype "passive"))
      (node (ref "C108") (pin "1") (pinfunction "1_1") (pintype "passive"))
      (node (ref "C109") (pin "1") (pinfunction "1_1") (pintype "passive"))
      (node (ref "C110") (pin "1") (pinfunction "1_1") (pintype "passive"))
      (node (ref "C111") (pin "1") (pinfunction "1_1") (pintype "passive"))
      (node (ref "C112") (pin "1") (pinfunction "1_1") (pintype "passive"))
      (node (ref "C113") (pin "1") (pinfunction "1_1") (pintype "passive"))
      (node (ref "C114") (pin "1") (pinfunction "1_1") (pintype "passive"))
      (node (ref "C17") (pin "1") (pinfunction "1_1") (pintype "passive"))
      (node (ref "C18") (pin "1") (pinfunction "1_1") (pintype "passive"))
      (node (ref "C19") (pin "1") (pinfunction "1_1") (pintype "passive"))
      (node (ref "C20") (pin "1") (pinfunction "1_1") (pintype "passive"))
      (node (ref "C21") (pin "1") (pinfunction "1_1") (pintype "passive"))
      (node (ref "C22") (pin "1") (pinfunction "1_1") (pintype "passive"))
      (node (ref "C23") (pin "1") (pinfunction "1_1") (pintype "passive"))
      (node (ref "C24") (pin "1") (pinfunction "1_1") (pintype "passive"))
      (node (ref "C25") (pin "1") (pinfunction "1_1") (pintype "passive"))
      (node (ref "D1") (pin "16") (pinfunction "VCC_16") (pintype "power_in"))
      (node (ref "D10") (pin "14") (pinfunction "VCC_14") (pintype "power_in"))
      (node (ref "D11") (pin "16") (pinfunction "VCC_16") (pintype "power_in"))
      (node (ref "D12") (pin "21") (pinfunction "~{WE}_21") (pintype "input"))
      (node (ref "D12") (pin "24") (pinfunction "VCC_24") (pintype "power_in"))
      (node (ref "D13") (pin "10") (pinfunction "PRE_10") (pintype "input"))
      (node (ref "D13") (pin "14") (pinfunction "VCC_14") (pintype "power_in"))
      (node (ref "D14") (pin "26") (pinfunction "VCC_26") (pintype "power_in"))
      (node (ref "D15") (pin "24") (pinfunction "VCC_24") (pintype "power_in"))
      (node (ref "D17") (pin "27") (pinfunction "~{WE}_27") (pintype "input"))
      (node (ref "D17") (pin "28") (pinfunction "VCC_28") (pintype "power_in"))
      (node (ref "D2") (pin "31") (pinfunction "VCC_31") (pintype "power_in"))
      (node (ref "D20") (pin "26") (pinfunction "VCC_26") (pintype "power_in"))
      (node (ref "D21") (pin "7") (pinfunction "V+_7") (pintype "power_in"))
      (node (ref "D22") (pin "28") (pinfunction "VCC_28") (pintype "power_in"))
      (node (ref "D3") (pin "5") (pinfunction "VCC_5") (pintype "power_in"))
      (node (ref "D30") (pin "20") (pinfunction "AVCC_20") (pintype "power_in"))
      (node (ref "D30") (pin "7") (pinfunction "VCC_7") (pintype "power_in"))
      (node (ref "D31") (pin "27") (pinfunction "~{WE}_27") (pintype "input"))
      (node (ref "D31") (pin "28") (pinfunction "VCC_28") (pintype "power_in"))
      (node (ref "D34") (pin "P$14") (pinfunction "+VOUT_P$14") (pintype "passive"))
      (node (ref "D35") (pin "P$1") (pinfunction "EN_P$1") (pintype "input"))
      (node (ref "D4") (pin "14") (pinfunction "VCC_14") (pintype "power_in"))
      (node (ref "D5") (pin "14") (pinfunction "VCC_14") (pintype "power_in"))
      (node (ref "D6") (pin "20") (pinfunction "VCC/+5V_20") (pintype "power_in"))
      (node (ref "D7") (pin "14") (pinfunction "~{CLR}_14") (pintype "input"))
      (node (ref "D7") (pin "24") (pinfunction "VCC_24") (pintype "power_in"))
      (node (ref "D8") (pin "40") (pinfunction "VCC_40") (pintype "power_in"))
      (node (ref "D9") (pin "14") (pinfunction "VCC_14") (pintype "power_in"))
      (node (ref "DIN1") (pin "P4") (pinfunction "4_P4") (pintype "passive"))
      (node (ref "ISP") (pin "2") (pinfunction "2_2") (pintype "passive"))
      (node (ref "LED") (pin "A") (pinfunction "A_A") (pintype "passive"))
      (node (ref "P14") (pin "25") (pinfunction "KL_25") (pintype "passive"))
      (node (ref "P20") (pin "25") (pinfunction "KL_25") (pintype "passive"))
      (node (ref "PIXEL_CLK") (pin "8") (pinfunction "VCC_8") (pintype "power_in"))
      (node (ref "R1") (pin "2") (pinfunction "2_2") (pintype "passive"))
      (node (ref "R104") (pin "1") (pinfunction "1_1") (pintype "passive"))
      (node (ref "R17") (pin "2") (pinfunction "2_2") (pintype "passive"))
      (node (ref "R3") (pin "2") (pinfunction "2_2") (pintype "passive"))
      (node (ref "R4") (pin "1") (pinfunction "1_1") (pintype "passive"))
      (node (ref "R5") (pin "1") (pinfunction "1_1") (pintype "passive"))
      (node (ref "R6-R12") (pin "1") (pinfunction "1_1") (pintype "passive"))
      (node (ref "VD1") (pin "C") (pinfunction "C_C") (pintype "passive"))
      (node (ref "VT2") (pin "1") (pinfunction "C_1") (pintype "passive"))
    )
    (net (code "2") (name "+12V") (class "Default")
      (node (ref "+12V") (pin "A") (pinfunction "A_A") (pintype "passive"))
      (node (ref "C11") (pin "1") (pinfunction "1_1") (pintype "passive"))
      (node (ref "C12") (pin "1") (pinfunction "1_1") (pintype "passive"))
      (node (ref "D1") (pin "9") (pinfunction "VDD_9") (pintype "power_in"))
      (node (ref "D35") (pin "P$14") (pinfunction "+VOUT_P$14") (pintype "passive"))
      (node (ref "D6") (pin "28") (pinfunction "VDD/+12V_28") (pintype "power_in"))
    )
    (net (code "3") (name "-5V") (class "Default")
      (node (ref "-5V") (pin "K") (pinfunction "C_K") (pintype "passive"))
      (node (ref "C10") (pin "1") (pinfunction "1_1") (pintype "passive"))
      (node (ref "C9") (pin "1") (pinfunction "1_1") (pintype "passive"))
      (node (ref "D21") (pin "4") (pinfunction "V-_4") (pintype "power_in"))
      (node (ref "D33") (pin "P$7") (pinfunction "-VOUT_P$7") (pintype "passive"))
      (node (ref "D6") (pin "11") (pinfunction "VBB/-5V_11") (pintype "power_in"))
      (node (ref "R107") (pin "2") (pinfunction "2_2") (pintype "passive"))
    )
    (net (code "4") (name "A0") (class "Default")
      (node (ref "D14") (pin "9") (pinfunction "A0_9") (pintype "input"))
      (node (ref "D17") (pin "10") (pinfunction "A0_10") (pintype "input"))
      (node (ref "D2") (pin "32") (pinfunction "A0_32") (pintype "bidirectional"))
      (node (ref "D20") (pin "9") (pinfunction "A0_9") (pintype "input"))
      (node (ref "D22") (pin "10") (pinfunction "A0_10") (pintype "input"))
      (node (ref "D6") (pin "25") (pinfunction "A0_25") (pintype "output"))
      (node (ref "D8") (pin "21") (pinfunction "A0_21") (pintype "input"))
    )
    (net (code "5") (name "A1") (class "Default")
      (node (ref "D14") (pin "8") (pinfunction "A1_8") (pintype "input"))
      (node (ref "D17") (pin "9") (pinfunction "A1_9") (pintype "input"))
      (node (ref "D2") (pin "33") (pinfunction "A1_33") (pintype "bidirectional"))
      (node (ref "D20") (pin "8") (pinfunction "A1_8") (pintype "input"))
      (node (ref "D22") (pin "9") (pinfunction "A1_9") (pintype "input"))
      (node (ref "D6") (pin "26") (pinfunction "A1_26") (pintype "output"))
    )
    (net (code "6") (name "A2") (class "Default")
      (node (ref "D17") (pin "8") (pinfunction "A2_8") (pintype "input"))
      (node (ref "D2") (pin "34") (pinfunction "A2_34") (pintype "bidirectional"))
      (node (ref "D22") (pin "8") (pinfunction "A2_8") (pintype "input"))
      (node (ref "D6") (pin "27") (pinfunction "A2_27") (pintype "output"))
    )
    (net (code "7") (name "A3") (class "Default")
      (node (ref "D17") (pin "7") (pinfunction "A3_7") (pintype "input"))
      (node (ref "D2") (pin "35") (pinfunction "A3_35") (pintype "bidirectional"))
      (node (ref "D22") (pin "7") (pinfunction "A3_7") (pintype "input"))
      (node (ref "D6") (pin "29") (pinfunction "A3_29") (pintype "output"))
    )
    (net (code "8") (name "A4") (class "Default")
      (node (ref "D17") (pin "6") (pinfunction "A4_6") (pintype "input"))
      (node (ref "D2") (pin "37") (pinfunction "A4_37") (pintype "tri_state"))
      (node (ref "D22") (pin "6") (pinfunction "A4_6") (pintype "input"))
      (node (ref "D6") (pin "30") (pinfunction "A4_30") (pintype "output"))
    )
    (net (code "9") (name "A5") (class "Default")
      (node (ref "D17") (pin "5") (pinfunction "A5_5") (pintype "input"))
      (node (ref "D2") (pin "38") (pinfunction "A5_38") (pintype "tri_state"))
      (node (ref "D22") (pin "5") (pinfunction "A5_5") (pintype "input"))
      (node (ref "D6") (pin "31") (pinfunction "A5_31") (pintype "output"))
    )
    (net (code "10") (name "A6") (class "Default")
      (node (ref "D17") (pin "4") (pinfunction "A6_4") (pintype "input"))
      (node (ref "D2") (pin "39") (pinfunction "A6_39") (pintype "tri_state"))
      (node (ref "D22") (pin "4") (pinfunction "A6_4") (pintype "input"))
      (node (ref "D6") (pin "32") (pinfunction "A6_32") (pintype "output"))
    )
    (net (code "11") (name "A7") (class "Default")
      (node (ref "D17") (pin "3") (pinfunction "A7_3") (pintype "input"))
      (node (ref "D2") (pin "40") (pinfunction "A7_40") (pintype "tri_state"))
      (node (ref "D22") (pin "3") (pinfunction "A7_3") (pintype "input"))
      (node (ref "D6") (pin "33") (pinfunction "A7_33") (pintype "output"))
    )
    (net (code "12") (name "A8") (class "Default")
      (node (ref "D17") (pin "25") (pinfunction "A8_25") (pintype "input"))
      (node (ref "D22") (pin "25") (pinfunction "A8_25") (pintype "input"))
      (node (ref "D6") (pin "34") (pinfunction "A8_34") (pintype "output"))
      (node (ref "D7") (pin "4") (pinfunction "Q0_4") (pintype "bidirectional"))
    )
    (net (code "13") (name "A9") (class "Default")
      (node (ref "D17") (pin "24") (pinfunction "A9_24") (pintype "input"))
      (node (ref "D22") (pin "24") (pinfunction "A9_24") (pintype "input"))
      (node (ref "D6") (pin "35") (pinfunction "A9_35") (pintype "output"))
      (node (ref "D7") (pin "6") (pinfunction "Q1_6") (pintype "bidirectional"))
    )
    (net (code "14") (name "A10") (class "Default")
      (node (ref "D17") (pin "21") (pinfunction "A10_21") (pintype "input"))
      (node (ref "D22") (pin "21") (pinfunction "A10_21") (pintype "input"))
      (node (ref "D6") (pin "1") (pinfunction "A10_1") (pintype "output"))
      (node (ref "D7") (pin "8") (pinfunction "Q2_8") (pintype "bidirectional"))
    )
    (net (code "15") (name "A11") (class "Default")
      (node (ref "D17") (pin "23") (pinfunction "A11_23") (pintype "input"))
      (node (ref "D22") (pin "23") (pinfunction "A11_23") (pintype "input"))
      (node (ref "D6") (pin "40") (pinfunction "A11_40") (pintype "output"))
      (node (ref "D7") (pin "10") (pinfunction "Q3_10") (pintype "bidirectional"))
    )
    (net (code "16") (name "A12") (class "Default")
      (node (ref "D11") (pin "1") (pinfunction "A_1") (pintype "input"))
      (node (ref "D17") (pin "2") (pinfunction "A12_2") (pintype "input"))
      (node (ref "D22") (pin "2") (pinfunction "A12_2") (pintype "input"))
      (node (ref "D6") (pin "37") (pinfunction "A12_37") (pintype "output"))
      (node (ref "D7") (pin "15") (pinfunction "Q4_15") (pintype "bidirectional"))
    )
    (net (code "17") (name "A13") (class "Default")
      (node (ref "D11") (pin "2") (pinfunction "B_2") (pintype "input"))
      (node (ref "D22") (pin "26") (pinfunction "A13_26") (pintype "input"))
      (node (ref "D6") (pin "38") (pinfunction "A13_38") (pintype "output"))
      (node (ref "D7") (pin "17") (pinfunction "Q5_17") (pintype "bidirectional"))
    )
    (net (code "18") (name "A14") (class "Default")
      (node (ref "D11") (pin "3") (pinfunction "C_3") (pintype "input"))
      (node (ref "D22") (pin "1") (pinfunction "A14_1") (pintype "input"))
      (node (ref "D6") (pin "39") (pinfunction "A14_39") (pintype "output"))
      (node (ref "D7") (pin "19") (pinfunction "Q6_19") (pintype "bidirectional"))
    )
    (net (code "19") (name "A15") (class "Default")
      (node (ref "D10") (pin "2") (pinfunction "I1_2") (pintype "input"))
      (node (ref "D11") (pin "6") (pinfunction "G1_6") (pintype "input"))
      (node (ref "D6") (pin "36") (pinfunction "A15_36") (pintype "output"))
      (node (ref "D7") (pin "21") (pinfunction "Q7_21") (pintype "bidirectional"))
      (node (ref "D9") (pin "9") (pinfunction "I_9") (pintype "input"))
    )
    (net (code "20") (name "CLK") (class "Default")
      (node (ref "D30") (pin "28") (pinfunction "PC5(ADC5/SCL)_28") (pintype "bidirectional"))
      (node (ref "DIN1") (pin "P5") (pinfunction "5_P5") (pintype "passive"))
      (node (ref "R104") (pin "5") (pinfunction "5_5") (pintype "passive"))
    )
    (net (code "21") (name "D0") (class "Default")
      (node (ref "D14") (pin "34") (pinfunction "D0_34") (pintype "bidirectional"))
      (node (ref "D17") (pin "11") (pinfunction "I/O0_11") (pintype "bidirectional"))
      (node (ref "D2") (pin "30") (pinfunction "D0_30") (pintype "bidirectional"))
      (node (ref "D20") (pin "34") (pinfunction "D0_34") (pintype "bidirectional"))
      (node (ref "D22") (pin "11") (pinfunction "I/O0_11") (pintype "bidirectional"))
      (node (ref "D6") (pin "10") (pinfunction "D0_10") (pintype "bidirectional"))
      (node (ref "D7") (pin "3") (pinfunction "D0_3") (pintype "bidirectional"))
      (node (ref "D8") (pin "12") (pinfunction "D0_12") (pintype "bidirectional"))
    )
    (net (code "22") (name "D1") (class "Default")
      (node (ref "D14") (pin "33") (pinfunction "D1_33") (pintype "bidirectional"))
      (node (ref "D17") (pin "12") (pinfunction "I/O1_12") (pintype "bidirectional"))
      (node (ref "D2") (pin "29") (pinfunction "D1_29") (pintype "bidirectional"))
      (node (ref "D20") (pin "33") (pinfunction "D1_33") (pintype "bidirectional"))
      (node (ref "D22") (pin "12") (pinfunction "I/O1_12") (pintype "bidirectional"))
      (node (ref "D6") (pin "9") (pinfunction "D1_9") (pintype "bidirectional"))
      (node (ref "D7") (pin "5") (pinfunction "D1_5") (pintype "bidirectional"))
      (node (ref "D8") (pin "13") (pinfunction "D1_13") (pintype "bidirectional"))
    )
    (net (code "23") (name "D2") (class "Default")
      (node (ref "D14") (pin "32") (pinfunction "D2_32") (pintype "bidirectional"))
      (node (ref "D17") (pin "13") (pinfunction "I/O2_13") (pintype "bidirectional"))
      (node (ref "D2") (pin "28") (pinfunction "D2_28") (pintype "bidirectional"))
      (node (ref "D20") (pin "32") (pinfunction "D2_32") (pintype "bidirectional"))
      (node (ref "D22") (pin "13") (pinfunction "I/O2_13") (pintype "bidirectional"))
      (node (ref "D6") (pin "8") (pinfunction "D2_8") (pintype "bidirectional"))
      (node (ref "D7") (pin "7") (pinfunction "D2_7") (pintype "bidirectional"))
      (node (ref "D8") (pin "14") (pinfunction "D2_14") (pintype "bidirectional"))
    )
    (net (code "24") (name "D3") (class "Default")
      (node (ref "D14") (pin "31") (pinfunction "D3_31") (pintype "bidirectional"))
      (node (ref "D17") (pin "15") (pinfunction "I/O3_15") (pintype "bidirectional"))
      (node (ref "D2") (pin "27") (pinfunction "D3_27") (pintype "bidirectional"))
      (node (ref "D20") (pin "31") (pinfunction "D3_31") (pintype "bidirectional"))
      (node (ref "D22") (pin "15") (pinfunction "I/O3_15") (pintype "bidirectional"))
      (node (ref "D6") (pin "7") (pinfunction "D3_7") (pintype "bidirectional"))
      (node (ref "D7") (pin "9") (pinfunction "D3_9") (pintype "bidirectional"))
      (node (ref "D8") (pin "15") (pinfunction "D3_15") (pintype "bidirectional"))
    )
    (net (code "25") (name "D4") (class "Default")
      (node (ref "D14") (pin "30") (pinfunction "D4_30") (pintype "bidirectional"))
      (node (ref "D17") (pin "16") (pinfunction "I/O4_16") (pintype "bidirectional"))
      (node (ref "D2") (pin "26") (pinfunction "D4_26") (pintype "bidirectional"))
      (node (ref "D20") (pin "30") (pinfunction "D4_30") (pintype "bidirectional"))
      (node (ref "D22") (pin "16") (pinfunction "I/O4_16") (pintype "bidirectional"))
      (node (ref "D6") (pin "3") (pinfunction "D4_3") (pintype "bidirectional"))
      (node (ref "D7") (pin "16") (pinfunction "D4_16") (pintype "bidirectional"))
      (node (ref "D8") (pin "16") (pinfunction "D4_16") (pintype "bidirectional"))
    )
    (net (code "26") (name "D5") (class "Default")
      (node (ref "D14") (pin "29") (pinfunction "D5_29") (pintype "bidirectional"))
      (node (ref "D17") (pin "17") (pinfunction "I/O5_17") (pintype "bidirectional"))
      (node (ref "D2") (pin "23") (pinfunction "D5_23") (pintype "bidirectional"))
      (node (ref "D20") (pin "29") (pinfunction "D5_29") (pintype "bidirectional"))
      (node (ref "D22") (pin "17") (pinfunction "I/O5_17") (pintype "bidirectional"))
      (node (ref "D6") (pin "4") (pinfunction "D5_4") (pintype "bidirectional"))
      (node (ref "D7") (pin "18") (pinfunction "D5_18") (pintype "bidirectional"))
      (node (ref "D8") (pin "17") (pinfunction "D5_17") (pintype "bidirectional"))
    )
    (net (code "27") (name "D6") (class "Default")
      (node (ref "D14") (pin "28") (pinfunction "D6_28") (pintype "bidirectional"))
      (node (ref "D17") (pin "18") (pinfunction "I/O6_18") (pintype "bidirectional"))
      (node (ref "D2") (pin "22") (pinfunction "D6_22") (pintype "bidirectional"))
      (node (ref "D20") (pin "28") (pinfunction "D6_28") (pintype "bidirectional"))
      (node (ref "D22") (pin "18") (pinfunction "I/O6_18") (pintype "bidirectional"))
      (node (ref "D6") (pin "5") (pinfunction "D6_5") (pintype "bidirectional"))
      (node (ref "D7") (pin "20") (pinfunction "D6_20") (pintype "bidirectional"))
      (node (ref "D8") (pin "18") (pinfunction "D6_18") (pintype "bidirectional"))
    )
    (net (code "28") (name "D7") (class "Default")
      (node (ref "D14") (pin "27") (pinfunction "D7_27") (pintype "bidirectional"))
      (node (ref "D17") (pin "19") (pinfunction "I/O7_19") (pintype "bidirectional"))
      (node (ref "D2") (pin "21") (pinfunction "D7_21") (pintype "bidirectional"))
      (node (ref "D20") (pin "27") (pinfunction "D7_27") (pintype "bidirectional"))
      (node (ref "D22") (pin "19") (pinfunction "I/O7_19") (pintype "bidirectional"))
      (node (ref "D6") (pin "6") (pinfunction "D7_6") (pintype "bidirectional"))
      (node (ref "D7") (pin "22") (pinfunction "D7_22") (pintype "bidirectional"))
      (node (ref "D8") (pin "19") (pinfunction "D7_19") (pintype "bidirectional"))
    )
    (net (code "29") (name "D14-PA0") (class "Default")
      (node (ref "D14") (pin "4") (pinfunction "PA0_4") (pintype "bidirectional"))
      (node (ref "D31") (pin "11") (pinfunction "I/O0_11") (pintype "tri_state"))
      (node (ref "P14") (pin "2") (pinfunction "KL_2") (pintype "passive"))
    )
    (net (code "30") (name "D14-PA1") (class "Default")
      (node (ref "D14") (pin "3") (pinfunction "PA1_3") (pintype "bidirectional"))
      (node (ref "D31") (pin "12") (pinfunction "I/O1_12") (pintype "tri_state"))
      (node (ref "P14") (pin "4") (pinfunction "KL_4") (pintype "passive"))
    )
    (net (code "31") (name "D14-PA2") (class "Default")
      (node (ref "D14") (pin "2") (pinfunction "PA2_2") (pintype "bidirectional"))
      (node (ref "D31") (pin "13") (pinfunction "I/O2_13") (pintype "tri_state"))
      (node (ref "P14") (pin "6") (pinfunction "KL_6") (pintype "passive"))
    )
    (net (code "32") (name "D14-PA3") (class "Default")
      (node (ref "D14") (pin "1") (pinfunction "PA3_1") (pintype "bidirectional"))
      (node (ref "D31") (pin "15") (pinfunction "I/O3_15") (pintype "tri_state"))
      (node (ref "P14") (pin "8") (pinfunction "KL_8") (pintype "passive"))
    )
    (net (code "33") (name "D14-PA4") (class "Default")
      (node (ref "D14") (pin "40") (pinfunction "PA4_40") (pintype "bidirectional"))
      (node (ref "D31") (pin "16") (pinfunction "I/O4_16") (pintype "tri_state"))
      (node (ref "P14") (pin "10") (pinfunction "KL_10") (pintype "passive"))
    )
    (net (code "34") (name "D14-PA5") (class "Default")
      (node (ref "D14") (pin "39") (pinfunction "PA5_39") (pintype "bidirectional"))
      (node (ref "D31") (pin "17") (pinfunction "I/O5_17") (pintype "tri_state"))
      (node (ref "P14") (pin "12") (pinfunction "KL_12") (pintype "passive"))
    )
    (net (code "35") (name "D14-PA6") (class "Default")
      (node (ref "D14") (pin "38") (pinfunction "PA6_38") (pintype "bidirectional"))
      (node (ref "D31") (pin "18") (pinfunction "I/O6_18") (pintype "tri_state"))
      (node (ref "P14") (pin "14") (pinfunction "KL_14") (pintype "passive"))
    )
    (net (code "36") (name "D14-PA7") (class "Default")
      (node (ref "D14") (pin "37") (pinfunction "PA7_37") (pintype "bidirectional"))
      (node (ref "D31") (pin "19") (pinfunction "I/O7_19") (pintype "tri_state"))
      (node (ref "P14") (pin "16") (pinfunction "KL_16") (pintype "passive"))
    )
    (net (code "37") (name "D14-PB0") (class "Default")
      (node (ref "D14") (pin "18") (pinfunction "PB0_18") (pintype "bidirectional"))
      (node (ref "D31") (pin "10") (pinfunction "A0_10") (pintype "input"))
      (node (ref "P14") (pin "18") (pinfunction "KL_18") (pintype "passive"))
    )
    (net (code "38") (name "D14-PB1") (class "Default")
      (node (ref "D14") (pin "19") (pinfunction "PB1_19") (pintype "bidirectional"))
      (node (ref "D31") (pin "9") (pinfunction "A1_9") (pintype "input"))
      (node (ref "P14") (pin "20") (pinfunction "KL_20") (pintype "passive"))
    )
    (net (code "39") (name "D14-PB2") (class "Default")
      (node (ref "D14") (pin "20") (pinfunction "PB2_20") (pintype "bidirectional"))
      (node (ref "D31") (pin "8") (pinfunction "A2_8") (pintype "input"))
      (node (ref "P14") (pin "22") (pinfunction "KL_22") (pintype "passive"))
    )
    (net (code "40") (name "D14-PB3") (class "Default")
      (node (ref "D14") (pin "21") (pinfunction "PB3_21") (pintype "bidirectional"))
      (node (ref "D31") (pin "7") (pinfunction "A3_7") (pintype "input"))
      (node (ref "P14") (pin "24") (pinfunction "KL_24") (pintype "passive"))
    )
    (net (code "41") (name "D14-PB4") (class "Default")
      (node (ref "D14") (pin "22") (pinfunction "PB4_22") (pintype "bidirectional"))
      (node (ref "D31") (pin "6") (pinfunction "A4_6") (pintype "input"))
      (node (ref "P14") (pin "23") (pinfunction "KL_23") (pintype "passive"))
    )
    (net (code "42") (name "D14-PB5") (class "Default")
      (node (ref "D14") (pin "23") (pinfunction "PB5_23") (pintype "bidirectional"))
      (node (ref "D31") (pin "5") (pinfunction "A5_5") (pintype "input"))
      (node (ref "P14") (pin "21") (pinfunction "KL_21") (pintype "passive"))
    )
    (net (code "43") (name "D14-PB6") (class "Default")
      (node (ref "D14") (pin "24") (pinfunction "PB6_24") (pintype "bidirectional"))
      (node (ref "D31") (pin "4") (pinfunction "A6_4") (pintype "input"))
      (node (ref "P14") (pin "19") (pinfunction "KL_19") (pintype "passive"))
    )
    (net (code "44") (name "D14-PB7") (class "Default")
      (node (ref "D14") (pin "25") (pinfunction "PB7_25") (pintype "bidirectional"))
      (node (ref "D31") (pin "3") (pinfunction "A7_3") (pintype "input"))
      (node (ref "P14") (pin "17") (pinfunction "KL_17") (pintype "passive"))
    )
    (net (code "45") (name "D14-PC0") (class "Default")
      (node (ref "D14") (pin "14") (pinfunction "PC0_14") (pintype "bidirectional"))
      (node (ref "D31") (pin "25") (pinfunction "A8_25") (pintype "input"))
      (node (ref "P14") (pin "1") (pinfunction "KL_1") (pintype "passive"))
    )
    (net (code "46") (name "D14-PC1") (class "Default")
      (node (ref "D14") (pin "15") (pinfunction "PC1_15") (pintype "bidirectional"))
      (node (ref "D31") (pin "24") (pinfunction "A9_24") (pintype "input"))
      (node (ref "P14") (pin "3") (pinfunction "KL_3") (pintype "passive"))
    )
    (net (code "47") (name "D14-PC2") (class "Default")
      (node (ref "D14") (pin "16") (pinfunction "PC2_16") (pintype "bidirectional"))
      (node (ref "D31") (pin "21") (pinfunction "A10_21") (pintype "input"))
      (node (ref "P14") (pin "5") (pinfunction "KL_5") (pintype "passive"))
    )
    (net (code "48") (name "D14-PC3") (class "Default")
      (node (ref "D14") (pin "17") (pinfunction "PC3_17") (pintype "bidirectional"))
      (node (ref "D31") (pin "23") (pinfunction "A11_23") (pintype "input"))
      (node (ref "P14") (pin "7") (pinfunction "KL_7") (pintype "passive"))
    )
    (net (code "49") (name "D14-PC4") (class "Default")
      (node (ref "D14") (pin "13") (pinfunction "PC4_13") (pintype "bidirectional"))
      (node (ref "D31") (pin "2") (pinfunction "A12_2") (pintype "input"))
      (node (ref "P14") (pin "9") (pinfunction "KL_9") (pintype "passive"))
    )
    (net (code "50") (name "D14-PC5") (class "Default")
      (node (ref "D14") (pin "12") (pinfunction "PC5_12") (pintype "bidirectional"))
      (node (ref "D31") (pin "26") (pinfunction "A13_26") (pintype "input"))
      (node (ref "P14") (pin "11") (pinfunction "KL_11") (pintype "passive"))
    )
    (net (code "51") (name "D14-PC6") (class "Default")
      (node (ref "D14") (pin "11") (pinfunction "PC6_11") (pintype "bidirectional"))
      (node (ref "D31") (pin "1") (pinfunction "A14_1") (pintype "input"))
      (node (ref "P14") (pin "13") (pinfunction "KL_13") (pintype "passive"))
    )
    (net (code "52") (name "D14-PC7") (class "Default")
      (node (ref "D14") (pin "10") (pinfunction "PC7_10") (pintype "bidirectional"))
      (node (ref "D31") (pin "22") (pinfunction "~{OE}_22") (pintype "input"))
      (node (ref "P14") (pin "15") (pinfunction "KL_15") (pintype "passive"))
    )
    (net (code "53") (name "D20-PA0") (class "Default")
      (node (ref "D20") (pin "4") (pinfunction "PA0_4") (pintype "bidirectional"))
      (node (ref "D30") (pin "2") (pinfunction "PD0(RXD)_2") (pintype "bidirectional"))
      (node (ref "P20") (pin "2") (pinfunction "KL_2") (pintype "passive"))
    )
    (net (code "54") (name "D20-PA1") (class "Default")
      (node (ref "D20") (pin "3") (pinfunction "PA1_3") (pintype "bidirectional"))
      (node (ref "D30") (pin "3") (pinfunction "PD1(TXD)_3") (pintype "bidirectional"))
      (node (ref "P20") (pin "4") (pinfunction "KL_4") (pintype "passive"))
    )
    (net (code "55") (name "D20-PA2") (class "Default")
      (node (ref "D20") (pin "2") (pinfunction "PA2_2") (pintype "bidirectional"))
      (node (ref "D30") (pin "4") (pinfunction "PD2(INT0)_4") (pintype "bidirectional"))
      (node (ref "P20") (pin "6") (pinfunction "KL_6") (pintype "passive"))
    )
    (net (code "56") (name "D20-PA3") (class "Default")
      (node (ref "D20") (pin "1") (pinfunction "PA3_1") (pintype "bidirectional"))
      (node (ref "D30") (pin "5") (pinfunction "PD3(INT1)_5") (pintype "bidirectional"))
      (node (ref "P20") (pin "8") (pinfunction "KL_8") (pintype "passive"))
    )
    (net (code "57") (name "D20-PA4") (class "Default")
      (node (ref "D20") (pin "40") (pinfunction "PA4_40") (pintype "bidirectional"))
      (node (ref "D30") (pin "6") (pinfunction "PD4(XCK/T0)_6") (pintype "bidirectional"))
      (node (ref "P20") (pin "10") (pinfunction "KL_10") (pintype "passive"))
    )
    (net (code "58") (name "D20-PA5") (class "Default")
      (node (ref "D20") (pin "39") (pinfunction "PA5_39") (pintype "bidirectional"))
      (node (ref "D30") (pin "11") (pinfunction "PD5(T1)_11") (pintype "bidirectional"))
      (node (ref "P20") (pin "12") (pinfunction "KL_12") (pintype "passive"))
    )
    (net (code "59") (name "D20-PA6") (class "Default")
      (node (ref "D20") (pin "38") (pinfunction "PA6_38") (pintype "bidirectional"))
      (node (ref "D30") (pin "12") (pinfunction "PD6(AIN0)_12") (pintype "bidirectional"))
      (node (ref "P20") (pin "14") (pinfunction "KL_14") (pintype "passive"))
    )
    (net (code "60") (name "D20-PA7") (class "Default")
      (node (ref "D20") (pin "37") (pinfunction "PA7_37") (pintype "bidirectional"))
      (node (ref "D30") (pin "13") (pinfunction "PD7(AIN1)_13") (pintype "bidirectional"))
      (node (ref "P20") (pin "16") (pinfunction "KL_16") (pintype "passive"))
    )
    (net (code "61") (name "D20-PB0") (class "Default")
      (node (ref "D20") (pin "18") (pinfunction "PB0_18") (pintype "bidirectional"))
      (node (ref "D30") (pin "14") (pinfunction "PB0(ICP)_14") (pintype "bidirectional"))
      (node (ref "P20") (pin "18") (pinfunction "KL_18") (pintype "passive"))
    )
    (net (code "62") (name "D20-PB1") (class "Default")
      (node (ref "D20") (pin "19") (pinfunction "PB1_19") (pintype "bidirectional"))
      (node (ref "D30") (pin "15") (pinfunction "PB1(OC1A)_15") (pintype "bidirectional"))
      (node (ref "P20") (pin "20") (pinfunction "KL_20") (pintype "passive"))
    )
    (net (code "63") (name "D20-PB2") (class "Default")
      (node (ref "D20") (pin "20") (pinfunction "PB2_20") (pintype "bidirectional"))
      (node (ref "D30") (pin "16") (pinfunction "PB2(SS/OC1B)_16") (pintype "bidirectional"))
      (node (ref "P20") (pin "22") (pinfunction "KL_22") (pintype "passive"))
    )
    (net (code "64") (name "D20-PB3") (class "Default")
      (node (ref "D20") (pin "21") (pinfunction "PB3_21") (pintype "bidirectional"))
      (node (ref "D30") (pin "17") (pinfunction "PB3(MOSI/OC2)_17") (pintype "bidirectional"))
      (node (ref "ISP") (pin "4") (pinfunction "4_4") (pintype "passive"))
      (node (ref "P20") (pin "24") (pinfunction "KL_24") (pintype "passive"))
    )
    (net (code "65") (name "D20-PB4") (class "Default")
      (node (ref "D20") (pin "22") (pinfunction "PB4_22") (pintype "bidirectional"))
      (node (ref "D30") (pin "18") (pinfunction "PB4(MISO)_18") (pintype "bidirectional"))
      (node (ref "ISP") (pin "1") (pinfunction "1_1") (pintype "passive"))
      (node (ref "P20") (pin "23") (pinfunction "KL_23") (pintype "passive"))
    )
    (net (code "66") (name "D20-PB5") (class "Default")
      (node (ref "D20") (pin "23") (pinfunction "PB5_23") (pintype "bidirectional"))
      (node (ref "D30") (pin "19") (pinfunction "PB5(SCK)_19") (pintype "bidirectional"))
      (node (ref "ISP") (pin "3") (pinfunction "3_3") (pintype "passive"))
      (node (ref "P20") (pin "21") (pinfunction "KL_21") (pintype "passive"))
    )
    (net (code "67") (name "D20-PB6") (class "Default")
      (node (ref "D20") (pin "24") (pinfunction "PB6_24") (pintype "bidirectional"))
      (node (ref "D30") (pin "9") (pinfunction "PB6(XTAL1/TOSC1)_9") (pintype "bidirectional"))
      (node (ref "P20") (pin "19") (pinfunction "KL_19") (pintype "passive"))
    )
    (net (code "68") (name "D20-PB7") (class "Default")
      (node (ref "D20") (pin "25") (pinfunction "PB7_25") (pintype "bidirectional"))
      (node (ref "D30") (pin "10") (pinfunction "PB7(XTAL2/TOSC2)_10") (pintype "bidirectional"))
      (node (ref "P20") (pin "17") (pinfunction "KL_17") (pintype "passive"))
    )
    (net (code "69") (name "D20-PC0") (class "Default")
      (node (ref "D20") (pin "14") (pinfunction "PC0_14") (pintype "bidirectional"))
      (node (ref "P20") (pin "1") (pinfunction "KL_1") (pintype "passive"))
      (node (ref "R32") (pin "1") (pinfunction "1_1") (pintype "passive"))
    )
    (net (code "70") (name "D20-PC1") (class "Default")
      (node (ref "D20") (pin "15") (pinfunction "PC1_15") (pintype "bidirectional"))
      (node (ref "P20") (pin "3") (pinfunction "KL_3") (pintype "passive"))
    )
    (net (code "71") (name "D20-PC2") (class "Default")
      (node (ref "D20") (pin "16") (pinfunction "PC2_16") (pintype "bidirectional"))
      (node (ref "P20") (pin "5") (pinfunction "KL_5") (pintype "passive"))
    )
    (net (code "72") (name "D20-PC3") (class "Default")
      (node (ref "D20") (pin "17") (pinfunction "PC3_17") (pintype "bidirectional"))
      (node (ref "D9") (pin "13") (pinfunction "I_13") (pintype "input"))
      (node (ref "P20") (pin "7") (pinfunction "KL_7") (pintype "passive"))
    )
    (net (code "73") (name "D20-PC4") (class "Default")
      (node (ref "D20") (pin "13") (pinfunction "PC4_13") (pintype "bidirectional"))
      (node (ref "P20") (pin "9") (pinfunction "KL_9") (pintype "passive"))
      (node (ref "R31") (pin "2") (pinfunction "2_2") (pintype "passive"))
      (node (ref "VD3") (pin "C") (pinfunction "C_C") (pintype "passive"))
    )
    (net (code "74") (name "D20-PC5") (class "Default")
      (node (ref "D20") (pin "12") (pinfunction "PC5_12") (pintype "bidirectional"))
      (node (ref "D30") (pin "23") (pinfunction "PC0(ADC0)_23") (pintype "bidirectional"))
      (node (ref "P20") (pin "11") (pinfunction "KL_11") (pintype "passive"))
    )
    (net (code "75") (name "D20-PC6") (class "Default")
      (node (ref "D20") (pin "11") (pinfunction "PC6_11") (pintype "bidirectional"))
      (node (ref "D30") (pin "24") (pinfunction "PC1(ADC1)_24") (pintype "bidirectional"))
      (node (ref "P20") (pin "13") (pinfunction "KL_13") (pintype "passive"))
    )
    (net (code "76") (name "D20-PC7") (class "Default")
      (node (ref "D20") (pin "10") (pinfunction "PC7_10") (pintype "bidirectional"))
      (node (ref "D30") (pin "25") (pinfunction "PC2(ADC2)_25") (pintype "bidirectional"))
      (node (ref "P20") (pin "15") (pinfunction "KL_15") (pintype "passive"))
    )
    (net (code "77") (name "DACK") (class "Default")
      (node (ref "D2") (pin "14") (pinfunction "~{DACK2}_14") (pintype "bidirectional"))
      (node (ref "D8") (pin "6") (pinfunction "DACK_6") (pintype "input"))
    )
    (net (code "78") (name "DATA") (class "Default")
      (node (ref "D30") (pin "27") (pinfunction "PC4(ADC4/SDA)_27") (pintype "bidirectional"))
      (node (ref "DIN1") (pin "P1") (pinfunction "1_P1") (pintype "passive"))
      (node (ref "R104") (pin "4") (pinfunction "4_4") (pintype "passive"))
    )
    (net (code "79") (name "DBIN") (class "Default")
      (node (ref "D10") (pin "1") (pinfunction "I0_1") (pintype "input"))
      (node (ref "D5") (pin "1") (pinfunction "I0_1") (pintype "input"))
      (node (ref "D6") (pin "17") (pinfunction "DBIN_17") (pintype "output"))
    )
    (net (code "80") (name "DMA_CLK") (class "Default")
      (node (ref "D1") (pin "6") (pinfunction "PHI2(TTL)_6") (pintype "output"))
      (node (ref "D2") (pin "12") (pinfunction "CLK_12") (pintype "input"))
    )
    (net (code "81") (name "DRQ") (class "Default")
      (node (ref "D2") (pin "17") (pinfunction "DRQ2_17") (pintype "bidirectional"))
      (node (ref "D8") (pin "5") (pinfunction "DRQ_5") (pintype "bidirectional"))
    )
    (net (code "82") (name "GND") (class "Default")
      (node (ref "24V_IN") (pin "2") (pinfunction "2_2") (pintype "passive"))
      (node (ref "24V_IN") (pin "3") (pinfunction "3_3") (pintype "passive"))
      (node (ref "C10") (pin "2") (pinfunction "2_2") (pintype "passive"))
      (node (ref "C101") (pin "2") (pinfunction "2_2") (pintype "passive"))
      (node (ref "C102") (pin "2") (pinfunction "2_2") (pintype "passive"))
      (node (ref "C103") (pin "1") (pinfunction "1_1") (pintype "passive"))
      (node (ref "C104") (pin "2") (pinfunction "2_2") (pintype "passive"))
      (node (ref "C105") (pin "2") (pinfunction "2_2") (pintype "passive"))
      (node (ref "C106") (pin "2") (pinfunction "2_2") (pintype "passive"))
      (node (ref "C107") (pin "2") (pinfunction "2_2") (pintype "passive"))
      (node (ref "C108") (pin "2") (pinfunction "2_2") (pintype "passive"))
      (node (ref "C109") (pin "2") (pinfunction "2_2") (pintype "passive"))
      (node (ref "C11") (pin "2") (pinfunction "2_2") (pintype "passive"))
      (node (ref "C110") (pin "2") (pinfunction "2_2") (pintype "passive"))
      (node (ref "C111") (pin "2") (pinfunction "2_2") (pintype "passive"))
      (node (ref "C112") (pin "2") (pinfunction "2_2") (pintype "passive"))
      (node (ref "C113") (pin "2") (pinfunction "2_2") (pintype "passive"))
      (node (ref "C114") (pin "2") (pinfunction "2_2") (pintype "passive"))
      (node (ref "C115") (pin "-") (pinfunction "-_-") (pintype "passive"))
      (node (ref "C116") (pin "-") (pinfunction "-_-") (pintype "passive"))
      (node (ref "C12") (pin "2") (pinfunction "2_2") (pintype "passive"))
      (node (ref "C17") (pin "2") (pinfunction "2_2") (pintype "passive"))
      (node (ref "C18") (pin "2") (pinfunction "2_2") (pintype "passive"))
      (node (ref "C19") (pin "2") (pinfunction "2_2") (pintype "passive"))
      (node (ref "C2") (pin "2") (pinfunction "2_2") (pintype "passive"))
      (node (ref "C20") (pin "2") (pinfunction "2_2") (pintype "passive"))
      (node (ref "C21") (pin "2") (pinfunction "2_2") (pintype "passive"))
      (node (ref "C22") (pin "2") (pinfunction "2_2") (pintype "passive"))
      (node (ref "C23") (pin "2") (pinfunction "2_2") (pintype "passive"))
      (node (ref "C24") (pin "2") (pinfunction "2_2") (pintype "passive"))
      (node (ref "C25") (pin "2") (pinfunction "2_2") (pintype "passive"))
      (node (ref "C6") (pin "2") (pinfunction "2_2") (pintype "passive"))
      (node (ref "C7") (pin "2") (pinfunction "2_2") (pintype "passive"))
      (node (ref "C9") (pin "2") (pinfunction "2_2") (pintype "passive"))
      (node (ref "D1") (pin "8") (pinfunction "GND_8") (pintype "power_in"))
      (node (ref "D10") (pin "7") (pinfunction "GND_7") (pintype "power_in"))
      (node (ref "D11") (pin "4") (pinfunction "G2A_4") (pintype "input"))
      (node (ref "D11") (pin "5") (pinfunction "G2B_5") (pintype "input"))
      (node (ref "D11") (pin "8") (pinfunction "GND_8") (pintype "power_in"))
      (node (ref "D12") (pin "12") (pinfunction "GND_12") (pintype "power_in"))
      (node (ref "D12") (pin "20") (pinfunction "~{OE}_20") (pintype "input"))
      (node (ref "D13") (pin "2") (pinfunction "D_2") (pintype "input"))
      (node (ref "D13") (pin "3") (pinfunction "CLK_3") (pintype "input"))
      (node (ref "D13") (pin "7") (pinfunction "GND_7") (pintype "power_in"))
      (node (ref "D14") (pin "7") (pinfunction "GND_7") (pintype "power_in"))
      (node (ref "D15") (pin "12") (pinfunction "GND_12") (pintype "power_in"))
      (node (ref "D17") (pin "14") (pinfunction "GND_14") (pintype "power_in"))
      (node (ref "D2") (pin "16") (pinfunction "DRQ3_16") (pintype "bidirectional"))
      (node (ref "D2") (pin "18") (pinfunction "DRQ1_18") (pintype "bidirectional"))
      (node (ref "D2") (pin "19") (pinfunction "DRQ0_19") (pintype "bidirectional"))
      (node (ref "D2") (pin "20") (pinfunction "GND_20") (pintype "power_in"))
      (node (ref "D20") (pin "7") (pinfunction "GND_7") (pintype "power_in"))
      (node (ref "D21") (pin "3") (pinfunction "+IN_3") (pintype "input"))
      (node (ref "D22") (pin "14") (pinfunction "VSS_14") (pintype "power_in"))
      (node (ref "D3") (pin "10") (pinfunction "GND_10") (pintype "power_in"))
      (node (ref "D3") (pin "6") (pinfunction "R0(1)_6") (pintype "input"))
      (node (ref "D3") (pin "7") (pinfunction "R0(2)_7") (pintype "input"))
      (node (ref "D30") (pin "22") (pinfunction "GND_22") (pintype "power_in"))
      (node (ref "D30") (pin "8") (pinfunction "GND_8") (pintype "power_in"))
      (node (ref "D31") (pin "14") (pinfunction "VSS_14") (pintype "power_in"))
      (node (ref "D31") (pin "20") (pinfunction "~{CE}_20") (pintype "input"))
      (node (ref "D32") (pin "3") (pinfunction "+IN_3") (pintype "input"))
      (node (ref "D32") (pin "4") (pinfunction "V-_4") (pintype "power_in"))
      (node (ref "D33") (pin "P$1") (pinfunction "-VIN_P$1") (pintype "input"))
      (node (ref "D33") (pin "P$3") (pinfunction "EN_P$3") (pintype "input"))
      (node (ref "D33") (pin "P$6") (pinfunction "+VOUT_P$6") (pintype "passive"))
      (node (ref "D34") (pin "P$16") (pinfunction "-VOUT_P$16") (pintype "passive"))
      (node (ref "D34") (pin "P$2") (pinfunction "-VIN_P$2") (pintype "input"))
      (node (ref "D34") (pin "P$3") (pinfunction "-VIN_P$3") (pintype "input"))
      (node (ref "D35") (pin "P$16") (pinfunction "-VOUT_P$16") (pintype "passive"))
      (node (ref "D35") (pin "P$2") (pinfunction "-VIN_P$2") (pintype "input"))
      (node (ref "D35") (pin "P$3") (pinfunction "-VIN_P$3") (pintype "input"))
      (node (ref "D4") (pin "7") (pinfunction "GND_7") (pintype "power_in"))
      (node (ref "D5") (pin "7") (pinfunction "GND_7") (pintype "power_in"))
      (node (ref "D6") (pin "14") (pinfunction "INT_14") (pintype "input"))
      (node (ref "D6") (pin "2") (pinfunction "VSS/GND_2") (pintype "power_in"))
      (node (ref "D7") (pin "1") (pinfunction "~{DS1}_1") (pintype "input"))
      (node (ref "D7") (pin "12") (pinfunction "GND_12") (pintype "power_in"))
      (node (ref "D7") (pin "2") (pinfunction "MODE_2") (pintype "input"))
      (node (ref "D8") (pin "20") (pinfunction "GND_20") (pintype "power_in"))
      (node (ref "D9") (pin "7") (pinfunction "GND_7") (pintype "power_in"))
      (node (ref "DIN1") (pin "P3") (pinfunction "3_P3") (pintype "passive"))
      (node (ref "EXT_RST") (pin "2") (pinfunction "2_2") (pintype "passive"))
      (node (ref "H1") (pin "2") (pinfunction "2_2") (pintype "passive"))
      (node (ref "ISP") (pin "6") (pinfunction "6_6") (pintype "passive"))
      (node (ref "P14") (pin "26") (pinfunction "KL_26") (pintype "passive"))
      (node (ref "P20") (pin "26") (pinfunction "KL_26") (pintype "passive"))
      (node (ref "PIXEL_CLK") (pin "4") (pinfunction "GND_4") (pintype "power_in"))
      (node (ref "R109") (pin "1") (pinfunction "1_1") (pintype "passive"))
      (node (ref "R110") (pin "1") (pinfunction "1_1") (pintype "passive"))
      (node (ref "R111") (pin "1") (pinfunction "1_1") (pintype "passive"))
      (node (ref "R19") (pin "1") (pinfunction "1_1") (pintype "passive"))
      (node (ref "R29") (pin "1") (pinfunction "1_1") (pintype "passive"))
      (node (ref "R30") (pin "1") (pinfunction "1_1") (pintype "passive"))
      (node (ref "R33") (pin "1") (pinfunction "1_1") (pintype "passive"))
      (node (ref "RESET") (pin "3") (pinfunction "P_3") (pintype "passive"))
      (node (ref "RESET") (pin "4") (pinfunction "P1_4") (pintype "passive"))
      (node (ref "TAPE_IN") (pin "S") (pinfunction "S_S") (pintype "passive"))
      (node (ref "TAPE_OUT") (pin "S") (pinfunction "S_S") (pintype "passive"))
      (node (ref "TVS1") (pin "A") (pinfunction "A_A") (pintype "passive"))
      (node (ref "VD3") (pin "A") (pinfunction "A_A") (pintype "passive"))
      (node (ref "VIDEO_OUT") (pin "S") (pinfunction "S_S") (pintype "passive"))
    )
    (net (code "83") (name "HLDA") (class "Default")
      (node (ref "D2") (pin "7") (pinfunction "HLDA_7") (pintype "input"))
      (node (ref "D6") (pin "21") (pinfunction "HLDA_21") (pintype "output"))
    )
    (net (code "84") (name "HOLD") (class "Default")
      (node (ref "D2") (pin "10") (pinfunction "HRQ_10") (pintype "bidirectional"))
      (node (ref "D6") (pin "13") (pinfunction "HOLD_13") (pintype "input"))
    )
    (net (code "85") (name "HSYNC") (class "Default")
      (node (ref "D5") (pin "4") (pinfunction "I0_4") (pintype "input"))
      (node (ref "D8") (pin "7") (pinfunction "HRTC_7") (pintype "bidirectional"))
    )
    (net (code "86") (name "Net-(+5V-C)") (class "Default")
      (node (ref "+5V") (pin "K") (pinfunction "C_K") (pintype "passive"))
      (node (ref "R111") (pin "2") (pinfunction "2_2") (pintype "passive"))
    )
    (net (code "87") (name "Net-(+12V-C)") (class "Default")
      (node (ref "+12V") (pin "K") (pinfunction "C_K") (pintype "passive"))
      (node (ref "R109") (pin "2") (pinfunction "2_2") (pintype "passive"))
    )
    (net (code "88") (name "Net-(-5V-PadA)") (class "Default")
      (node (ref "-5V") (pin "A") (pinfunction "A_A") (pintype "passive"))
      (node (ref "R110") (pin "2") (pinfunction "2_2") (pintype "passive"))
    )
    (net (code "89") (name "Net-(24V_IN-Pad1)") (class "Default")
      (node (ref "24V_IN") (pin "1") (pinfunction "1_1") (pintype "passive"))
      (node (ref "F1") (pin "1") (pinfunction "1_1") (pintype "passive"))
    )
    (net (code "90") (name "Net-(C3-Pad+)") (class "Default")
      (node (ref "C3") (pin "+") (pinfunction "+_+") (pintype "passive"))
      (node (ref "C4") (pin "1") (pinfunction "1_1") (pintype "passive"))
      (node (ref "R18") (pin "1") (pinfunction "1_1") (pintype "passive"))
      (node (ref "R19") (pin "2") (pinfunction "2_2") (pintype "passive"))
    )
    (net (code "91") (name "Net-(C3-Pad-)") (class "Default")
      (node (ref "C3") (pin "-") (pinfunction "-_-") (pintype "passive"))
      (node (ref "C4") (pin "2") (pinfunction "2_2") (pintype "passive"))
      (node (ref "VIDEO_OUT") (pin "T") (pinfunction "T_T") (pintype "passive"))
    )
    (net (code "92") (name "Net-(C5-Pad1)") (class "Default")
      (node (ref "C5") (pin "1") (pinfunction "1_1") (pintype "passive"))
      (node (ref "R29") (pin "2") (pinfunction "2_2") (pintype "passive"))
      (node (ref "TAPE_IN") (pin "T") (pinfunction "T_T") (pintype "passive"))
    )
    (net (code "93") (name "Net-(C7-Pad1)") (class "Default")
      (node (ref "C7") (pin "1") (pinfunction "1_1") (pintype "passive"))
      (node (ref "C8") (pin "1") (pinfunction "1_1") (pintype "passive"))
      (node (ref "R32") (pin "2") (pinfunction "2_2") (pintype "passive"))
      (node (ref "R33") (pin "2") (pinfunction "2_2") (pintype "passive"))
    )
    (net (code "94") (name "Net-(C8-Pad2)") (class "Default")
      (node (ref "C8") (pin "2") (pinfunction "2_2") (pintype "passive"))
      (node (ref "TAPE_OUT") (pin "T") (pinfunction "T_T") (pintype "passive"))
    )
    (net (code "95") (name "Net-(D1-PHI1)") (class "Default")
      (node (ref "D1") (pin "11") (pinfunction "PHI1_11") (pintype "output"))
      (node (ref "D6") (pin "22") (pinfunction "PHI1_22") (pintype "input"))
    )
    (net (code "96") (name "Net-(D1-PHI2)") (class "Default")
      (node (ref "D1") (pin "10") (pinfunction "PHI2_10") (pintype "output"))
      (node (ref "D6") (pin "15") (pinfunction "PHI2_15") (pintype "input"))
    )
    (net (code "97") (name "Net-(D1-RDYIN)") (class "Default")
      (node (ref "D1") (pin "3") (pinfunction "RDYIN_3") (pintype "input"))
      (node (ref "R3") (pin "1") (pinfunction "1_1") (pintype "passive"))
    )
    (net (code "98") (name "Net-(D1-SYNC)") (class "Default")
      (node (ref "D1") (pin "5") (pinfunction "SYNC_5") (pintype "input"))
      (node (ref "D6") (pin "19") (pinfunction "SYNC_19") (pintype "output"))
    )
    (net (code "99") (name "Net-(D1-XTAL1)") (class "Default")
      (node (ref "D1") (pin "15") (pinfunction "XTAL1_15") (pintype "input"))
      (node (ref "Z1") (pin "2") (pinfunction "2_2") (pintype "passive"))
    )
    (net (code "100") (name "Net-(D1-XTAL2)") (class "Default")
      (node (ref "D1") (pin "14") (pinfunction "XTAL2_14") (pintype "input"))
      (node (ref "Z1") (pin "1") (pinfunction "1_1") (pintype "passive"))
    )
    (net (code "101") (name "Net-(D2A-ADSTB)") (class "Default")
      (node (ref "D2") (pin "8") (pinfunction "ADSTB_8") (pintype "bidirectional"))
      (node (ref "D7") (pin "11") (pinfunction "STROBE_11") (pintype "input"))
    )
    (net (code "102") (name "Net-(D2A-AEN)") (class "Default")
      (node (ref "D2") (pin "9") (pinfunction "AEN_9") (pintype "bidirectional"))
      (node (ref "D7") (pin "13") (pinfunction "DS2_13") (pintype "input"))
    )
    (net (code "103") (name "Net-(D3A-CKA)") (class "Default")
      (node (ref "D3") (pin "14") (pinfunction "CKA_14") (pintype "input"))
      (node (ref "PIXEL_CLK") (pin "5") (pinfunction "OUT_5") (pintype "output"))
    )
    (net (code "104") (name "Net-(D3A-QC)") (class "Default")
      (node (ref "D3") (pin "9") (pinfunction "QC_9") (pintype "output"))
      (node (ref "D4") (pin "5") (pinfunction "I1_5") (pintype "input"))
    )
    (net (code "105") (name "Net-(D3A-QD)") (class "Default")
      (node (ref "D3") (pin "8") (pinfunction "QD_8") (pintype "output"))
      (node (ref "D4") (pin "4") (pinfunction "I0_4") (pintype "input"))
      (node (ref "D8") (pin "30") (pinfunction "CCLK_30") (pintype "input"))
    )
    (net (code "106") (name "Net-(D4A-O)") (class "Default")
      (node (ref "D4") (pin "3") (pinfunction "O_3") (pintype "output"))
      (node (ref "D8") (pin "10") (pinfunction "WR_10") (pintype "input"))
    )
    (net (code "107") (name "Net-(D4C-I1)") (class "Default")
      (node (ref "D4") (pin "10") (pinfunction "I1_10") (pintype "input"))
      (node (ref "D4") (pin "11") (pinfunction "O_11") (pintype "output"))
    )
    (net (code "108") (name "Net-(D5B-O)") (class "Default")
      (node (ref "D5") (pin "6") (pinfunction "O_6") (pintype "output"))
      (node (ref "D9") (pin "5") (pinfunction "I_5") (pintype "input"))
    )
    (net (code "109") (name "Net-(D5C-I0)") (class "Default")
      (node (ref "D5") (pin "9") (pinfunction "I0_9") (pintype "input"))
      (node (ref "R5") (pin "6") (pinfunction "6_6") (pintype "passive"))
    )
    (net (code "110") (name "Net-(D5C-I1)") (class "Default")
      (node (ref "D5") (pin "10") (pinfunction "I1_10") (pintype "input"))
      (node (ref "R5") (pin "5") (pinfunction "5_5") (pintype "passive"))
    )
    (net (code "111") (name "Net-(D5D-I0)") (class "Default")
      (node (ref "D5") (pin "12") (pinfunction "I0_12") (pintype "input"))
      (node (ref "R5") (pin "3") (pinfunction "3_3") (pintype "passive"))
    )
    (net (code "112") (name "Net-(D5D-I1)") (class "Default")
      (node (ref "D5") (pin "13") (pinfunction "I1_13") (pintype "input"))
      (node (ref "R5") (pin "2") (pinfunction "2_2") (pintype "passive"))
    )
    (net (code "113") (name "Net-(D6-INTE)") (class "Default")
      (node (ref "D6") (pin "16") (pinfunction "INTE_16") (pintype "output"))
      (node (ref "D9") (pin "1") (pinfunction "I_1") (pintype "input"))
    )
    (net (code "114") (name "Net-(D9A-O)") (class "Default")
      (node (ref "D9") (pin "2") (pinfunction "O_2") (pintype "output"))
      (node (ref "R101") (pin "1") (pinfunction "1_1") (pintype "passive"))
    )
    (net (code "115") (name "Net-(D9F-O)") (class "Default")
      (node (ref "D9") (pin "12") (pinfunction "O_12") (pintype "output"))
      (node (ref "R103") (pin "1") (pinfunction "1_1") (pintype "passive"))
    )
    (net (code "116") (name "Net-(D10A-O)") (class "Default")
      (node (ref "D10") (pin "3") (pinfunction "O_3") (pintype "output"))
      (node (ref "D13") (pin "4") (pinfunction "PRE_4") (pintype "input"))
    )
    (net (code "117") (name "Net-(D10B-I0)") (class "Default")
      (node (ref "D10") (pin "4") (pinfunction "I0_4") (pintype "input"))
      (node (ref "D9") (pin "8") (pinfunction "O_8") (pintype "output"))
    )
    (net (code "118") (name "Net-(D10C-I0)") (class "Default")
      (node (ref "D10") (pin "9") (pinfunction "I0_9") (pintype "input"))
      (node (ref "R4") (pin "6") (pinfunction "6_6") (pintype "passive"))
    )
    (net (code "119") (name "Net-(D10C-I1)") (class "Default")
      (node (ref "D10") (pin "10") (pinfunction "I1_10") (pintype "input"))
      (node (ref "R4") (pin "5") (pinfunction "5_5") (pintype "passive"))
    )
    (net (code "120") (name "Net-(D10D-I0)") (class "Default")
      (node (ref "D10") (pin "12") (pinfunction "I0_12") (pintype "input"))
      (node (ref "R4") (pin "3") (pinfunction "3_3") (pintype "passive"))
    )
    (net (code "121") (name "Net-(D10D-I1)") (class "Default")
      (node (ref "D10") (pin "13") (pinfunction "I1_13") (pintype "input"))
      (node (ref "R4") (pin "2") (pinfunction "2_2") (pintype "passive"))
    )
    (net (code "122") (name "Net-(D11A-Y7)") (class "Default")
      (node (ref "D11") (pin "7") (pinfunction "Y7_7") (pintype "output"))
      (node (ref "D4") (pin "13") (pinfunction "I1_13") (pintype "input"))
    )
    (net (code "123") (name "Net-(D12A-A0)") (class "Default")
      (node (ref "D12") (pin "8") (pinfunction "A0_8") (pintype "input"))
      (node (ref "D8") (pin "4") (pinfunction "LC0_4") (pintype "bidirectional"))
    )
    (net (code "124") (name "Net-(D12A-A1)") (class "Default")
      (node (ref "D12") (pin "7") (pinfunction "A1_7") (pintype "input"))
      (node (ref "D8") (pin "3") (pinfunction "LC1_3") (pintype "bidirectional"))
    )
    (net (code "125") (name "Net-(D12A-A2)") (class "Default")
      (node (ref "D12") (pin "6") (pinfunction "A2_6") (pintype "input"))
      (node (ref "D8") (pin "2") (pinfunction "LC2_2") (pintype "bidirectional"))
    )
    (net (code "126") (name "Net-(D12A-A3)") (class "Default")
      (node (ref "D12") (pin "5") (pinfunction "A3_5") (pintype "input"))
      (node (ref "D8") (pin "23") (pinfunction "CC0_23") (pintype "bidirectional"))
    )
    (net (code "127") (name "Net-(D12A-A4)") (class "Default")
      (node (ref "D12") (pin "4") (pinfunction "A4_4") (pintype "input"))
      (node (ref "D8") (pin "24") (pinfunction "CC1_24") (pintype "bidirectional"))
    )
    (net (code "128") (name "Net-(D12A-A5)") (class "Default")
      (node (ref "D12") (pin "3") (pinfunction "A5_3") (pintype "input"))
      (node (ref "D8") (pin "25") (pinfunction "CC2_25") (pintype "bidirectional"))
    )
    (net (code "129") (name "Net-(D12A-A6)") (class "Default")
      (node (ref "D12") (pin "2") (pinfunction "A6_2") (pintype "input"))
      (node (ref "D8") (pin "26") (pinfunction "CC3_26") (pintype "bidirectional"))
    )
    (net (code "130") (name "Net-(D12A-A7)") (class "Default")
      (node (ref "D12") (pin "1") (pinfunction "A7_1") (pintype "input"))
      (node (ref "D8") (pin "27") (pinfunction "CC4_27") (pintype "bidirectional"))
    )
    (net (code "131") (name "Net-(D12A-A8)") (class "Default")
      (node (ref "D12") (pin "23") (pinfunction "A8_23") (pintype "input"))
      (node (ref "D8") (pin "28") (pinfunction "CC5_28") (pintype "bidirectional"))
    )
    (net (code "132") (name "Net-(D12A-A9)") (class "Default")
      (node (ref "D12") (pin "22") (pinfunction "A9_22") (pintype "input"))
      (node (ref "D8") (pin "29") (pinfunction "CC6_29") (pintype "bidirectional"))
    )
    (net (code "133") (name "Net-(D12A-A10)") (class "Default")
      (node (ref "D12") (pin "19") (pinfunction "A10_19") (pintype "input"))
      (node (ref "D8") (pin "33") (pinfunction "GPA0_33") (pintype "bidirectional"))
    )
    (net (code "134") (name "Net-(D12A-D0)") (class "Default")
      (node (ref "D12") (pin "9") (pinfunction "D0_9") (pintype "bidirectional"))
      (node (ref "D15") (pin "3") (pinfunction "A_3") (pintype "input"))
      (node (ref "R6-R12") (pin "7") (pinfunction "7_7") (pintype "passive"))
    )
    (net (code "135") (name "Net-(D12A-D1)") (class "Default")
      (node (ref "D12") (pin "10") (pinfunction "D1_10") (pintype "bidirectional"))
      (node (ref "D15") (pin "5") (pinfunction "B_5") (pintype "input"))
      (node (ref "R6-R12") (pin "6") (pinfunction "6_6") (pintype "passive"))
    )
    (net (code "136") (name "Net-(D12A-D2)") (class "Default")
      (node (ref "D12") (pin "11") (pinfunction "D2_11") (pintype "bidirectional"))
      (node (ref "D15") (pin "7") (pinfunction "C_7") (pintype "input"))
      (node (ref "R6-R12") (pin "5") (pinfunction "5_5") (pintype "passive"))
    )
    (net (code "137") (name "Net-(D12A-D3)") (class "Default")
      (node (ref "D12") (pin "13") (pinfunction "D3_13") (pintype "bidirectional"))
      (node (ref "D15") (pin "9") (pinfunction "D_9") (pintype "input"))
      (node (ref "R6-R12") (pin "2") (pinfunction "2_2") (pintype "passive"))
    )
    (net (code "138") (name "Net-(D12A-D4)") (class "Default")
      (node (ref "D12") (pin "14") (pinfunction "D4_14") (pintype "bidirectional"))
      (node (ref "D15") (pin "15") (pinfunction "E_15") (pintype "input"))
      (node (ref "R6-R12") (pin "3") (pinfunction "3_3") (pintype "passive"))
    )
    (net (code "139") (name "Net-(D12A-D5)") (class "Default")
      (node (ref "D12") (pin "15") (pinfunction "D5_15") (pintype "bidirectional"))
      (node (ref "D15") (pin "17") (pinfunction "F_17") (pintype "input"))
      (node (ref "R6-R12") (pin "4") (pinfunction "4_4") (pintype "passive"))
    )
    (net (code "140") (name "Net-(D12A-~{CE})") (class "Default")
      (node (ref "D12") (pin "18") (pinfunction "~{CE}_18") (pintype "input"))
      (node (ref "D8") (pin "35") (pinfunction "VSP_35") (pintype "bidirectional"))
    )
    (net (code "141") (name "Net-(D13A-CLR)") (class "Default")
      (node (ref "D13") (pin "1") (pinfunction "CLR_1") (pintype "input"))
      (node (ref "D9") (pin "4") (pinfunction "O_4") (pintype "output"))
    )
    (net (code "142") (name "Net-(D13B-CLK)") (class "Default")
      (node (ref "D13") (pin "11") (pinfunction "CLK_11") (pintype "input"))
      (node (ref "D15") (pin "23") (pinfunction "S1_23") (pintype "input"))
      (node (ref "D4") (pin "6") (pinfunction "O_6") (pintype "output"))
    )
    (net (code "143") (name "Net-(D13B-CLR)") (class "Default")
      (node (ref "D13") (pin "13") (pinfunction "CLR_13") (pintype "input"))
      (node (ref "D15") (pin "20") (pinfunction "QH_20") (pintype "output"))
    )
    (net (code "144") (name "Net-(D13B-D)") (class "Default")
      (node (ref "D13") (pin "12") (pinfunction "D_12") (pintype "input"))
      (node (ref "D8") (pin "37") (pinfunction "LTEN_37") (pintype "bidirectional"))
    )
    (net (code "145") (name "Net-(D13B-~{Q})") (class "Default")
      (node (ref "D13") (pin "8") (pinfunction "~{Q}_8") (pintype "output"))
      (node (ref "D15") (pin "13") (pinfunction "CLR_13") (pintype "input"))
    )
    (net (code "146") (name "Net-(D15A-CLK)") (class "Default")
      (node (ref "D15") (pin "11") (pinfunction "CLK_11") (pintype "input"))
      (node (ref "D3") (pin "1") (pinfunction "CKB_1") (pintype "input"))
      (node (ref "D3") (pin "12") (pinfunction "QA_12") (pintype "output"))
    )
    (net (code "147") (name "Net-(D15A-G)") (class "Default")
      (node (ref "D15") (pin "1") (pinfunction "S0_1") (pintype "input"))
      (node (ref "D15") (pin "19") (pinfunction "G_19") (pintype "input"))
      (node (ref "D15") (pin "2") (pinfunction "SR_2") (pintype "input"))
      (node (ref "D15") (pin "21") (pinfunction "H_21") (pintype "input"))
      (node (ref "D15") (pin "22") (pinfunction "SL_22") (pintype "input"))
      (node (ref "R6-R12") (pin "8") (pinfunction "8_8") (pintype "passive"))
    )
    (net (code "148") (name "Net-(D15A-QF)") (class "Default")
      (node (ref "D15") (pin "16") (pinfunction "QF_16") (pintype "output"))
      (node (ref "D9") (pin "11") (pinfunction "I_11") (pintype "input"))
    )
    (net (code "149") (name "Net-(D21--IN)") (class "Default")
      (node (ref "C5") (pin "2") (pinfunction "2_2") (pintype "passive"))
      (node (ref "C6") (pin "1") (pinfunction "1_1") (pintype "passive"))
      (node (ref "D21") (pin "2") (pinfunction "-IN_2") (pintype "input"))
      (node (ref "R30") (pin "2") (pinfunction "2_2") (pintype "passive"))
    )
    (net (code "150") (name "Net-(D21-OUT)") (class "Default")
      (node (ref "D21") (pin "6") (pinfunction "OUT_6") (pintype "output"))
      (node (ref "R31") (pin "1") (pinfunction "1_1") (pintype "passive"))
    )
    (net (code "151") (name "Net-(D30-AREF)") (class "Default")
      (node (ref "C103") (pin "2") (pinfunction "2_2") (pintype "passive"))
      (node (ref "D30") (pin "21") (pinfunction "AREF_21") (pintype "passive"))
    )
    (net (code "152") (name "Net-(D30-PC3(ADC3))") (class "Default")
      (node (ref "D30") (pin "26") (pinfunction "PC3(ADC3)_26") (pintype "bidirectional"))
      (node (ref "VD101") (pin "C") (pinfunction "C_C") (pintype "passive"))
    )
    (net (code "153") (name "Net-(D30-PC6({slash}RESET))") (class "Default")
      (node (ref "D30") (pin "1") (pinfunction "PC6(/RESET)_1") (pintype "bidirectional"))
      (node (ref "ISP") (pin "5") (pinfunction "5_5") (pintype "passive"))
      (node (ref "R104") (pin "6") (pinfunction "6_6") (pintype "passive"))
    )
    (net (code "154") (name "Net-(D32--IN)") (class "Default")
      (node (ref "D32") (pin "2") (pinfunction "-IN_2") (pintype "input"))
      (node (ref "R107") (pin "1") (pinfunction "1_1") (pintype "passive"))
      (node (ref "R108") (pin "2") (pinfunction "2_2") (pintype "passive"))
    )
    (net (code "155") (name "Net-(D32-OUT)") (class "Default")
      (node (ref "D32") (pin "6") (pinfunction "OUT_6") (pintype "output"))
      (node (ref "D34") (pin "P$1") (pinfunction "EN_P$1") (pintype "input"))
      (node (ref "R108") (pin "1") (pinfunction "1_1") (pintype "passive"))
    )
    (net (code "156") (name "Net-(D32-V+)") (class "Default")
      (node (ref "C115") (pin "+") (pinfunction "+_+") (pintype "passive"))
      (node (ref "C116") (pin "+") (pinfunction "+_+") (pintype "passive"))
      (node (ref "D32") (pin "7") (pinfunction "V+_7") (pintype "power_in"))
      (node (ref "D33") (pin "P$2") (pinfunction "+VIN_P$2") (pintype "input"))
      (node (ref "D34") (pin "P$22") (pinfunction "+VIN_P$22") (pintype "input"))
      (node (ref "D34") (pin "P$23") (pinfunction "+VIN_P$23") (pintype "input"))
      (node (ref "D35") (pin "P$22") (pinfunction "+VIN_P$22") (pintype "input"))
      (node (ref "D35") (pin "P$23") (pinfunction "+VIN_P$23") (pintype "input"))
      (node (ref "F1") (pin "2") (pinfunction "2_2") (pintype "passive"))
      (node (ref "TVS1") (pin "C") (pinfunction "C_C") (pintype "passive"))
    )
    (net (code "157") (name "Net-(H1-Pad1)") (class "Default")
      (node (ref "H1") (pin "1") (pinfunction "1_1") (pintype "passive"))
      (node (ref "R101") (pin "2") (pinfunction "2_2") (pintype "passive"))
    )
    (net (code "158") (name "Net-(LED-C)") (class "Default")
      (node (ref "LED") (pin "K") (pinfunction "C_K") (pintype "passive"))
      (node (ref "R103") (pin "2") (pinfunction "2_2") (pintype "passive"))
    )
    (net (code "159") (name "Net-(VT2-B)") (class "Default")
      (node (ref "R15") (pin "1") (pinfunction "1_1") (pintype "passive"))
      (node (ref "R16") (pin "2") (pinfunction "2_2") (pintype "passive"))
      (node (ref "R17") (pin "1") (pinfunction "1_1") (pintype "passive"))
      (node (ref "VT2") (pin "2") (pinfunction "B_2") (pintype "passive"))
    )
    (net (code "160") (name "Net-(VT2-E)") (class "Default")
      (node (ref "R18") (pin "2") (pinfunction "2_2") (pintype "passive"))
      (node (ref "VT2") (pin "3") (pinfunction "E_3") (pintype "passive"))
    )
    (net (code "161") (name "READY") (class "Default")
      (node (ref "D1") (pin "4") (pinfunction "READY_4") (pintype "output"))
      (node (ref "D2") (pin "6") (pinfunction "READY_6") (pintype "input"))
      (node (ref "D6") (pin "23") (pinfunction "READY_23") (pintype "input"))
    )
    (net (code "162") (name "RESET") (class "Default")
      (node (ref "D1") (pin "1") (pinfunction "RESET_1") (pintype "output"))
      (node (ref "D14") (pin "35") (pinfunction "RESET_35") (pintype "input"))
      (node (ref "D2") (pin "13") (pinfunction "RESET_13") (pintype "input"))
      (node (ref "D20") (pin "35") (pinfunction "RESET_35") (pintype "input"))
      (node (ref "D6") (pin "12") (pinfunction "RESET_12") (pintype "input"))
      (node (ref "D9") (pin "3") (pinfunction "I_3") (pintype "input"))
    )
    (net (code "163") (name "VIDEO") (class "Default")
      (node (ref "D9") (pin "10") (pinfunction "O_10") (pintype "output"))
      (node (ref "R15") (pin "2") (pinfunction "2_2") (pintype "passive"))
    )
    (net (code "164") (name "VSYNC") (class "Default")
      (node (ref "D5") (pin "5") (pinfunction "I1_5") (pintype "input"))
      (node (ref "D8") (pin "8") (pinfunction "VRTC_8") (pintype "bidirectional"))
    )
    (net (code "165") (name "unconnected-(D1-OSC-Pad12)") (class "Default")
      (node (ref "D1") (pin "12") (pinfunction "OSC_12") (pintype "output"))
    )
    (net (code "166") (name "unconnected-(D1-STSTB-Pad7)") (class "Default")
      (node (ref "D1") (pin "7") (pinfunction "STSTB_7") (pintype "output"))
    )
    (net (code "167") (name "unconnected-(D1-TANK-Pad13)") (class "Default")
      (node (ref "D1") (pin "13") (pinfunction "TANK_13") (pintype "input"))
    )
    (net (code "168") (name "unconnected-(D2A-MARK-Pad5)") (class "Default")
      (node (ref "D2") (pin "5") (pinfunction "MARK_5") (pintype "output"))
    )
    (net (code "169") (name "unconnected-(D2A-TC-Pad36)") (class "Default")
      (node (ref "D2") (pin "36") (pinfunction "TC_36") (pintype "bidirectional"))
    )
    (net (code "170") (name "unconnected-(D2A-~{DACK0}-Pad25)") (class "Default")
      (node (ref "D2") (pin "25") (pinfunction "~{DACK0}_25") (pintype "bidirectional"))
    )
    (net (code "171") (name "unconnected-(D2A-~{DACK1}-Pad24)") (class "Default")
      (node (ref "D2") (pin "24") (pinfunction "~{DACK1}_24") (pintype "bidirectional"))
    )
    (net (code "172") (name "unconnected-(D2A-~{DACK3}-Pad15)") (class "Default")
      (node (ref "D2") (pin "15") (pinfunction "~{DACK3}_15") (pintype "bidirectional"))
    )
    (net (code "173") (name "unconnected-(D2A-~{MEMR}-Pad3)") (class "Default")
      (node (ref "D2") (pin "3") (pinfunction "~{MEMR}_3") (pintype "bidirectional"))
    )
    (net (code "174") (name "unconnected-(D3A-QB-Pad11)") (class "Default")
      (node (ref "D3") (pin "11") (pinfunction "QB_11") (pintype "output"))
    )
    (net (code "175") (name "unconnected-(D5C-O-Pad8)") (class "Default")
      (node (ref "D5") (pin "8") (pinfunction "O_8") (pintype "output"))
    )
    (net (code "176") (name "unconnected-(D5D-O-Pad11)") (class "Default")
      (node (ref "D5") (pin "11") (pinfunction "O_11") (pintype "output"))
    )
    (net (code "177") (name "unconnected-(D6-WAIT-Pad24)") (class "Default")
      (node (ref "D6") (pin "24") (pinfunction "WAIT_24") (pintype "output"))
    )
    (net (code "178") (name "unconnected-(D7A-~{INT}-Pad23)") (class "Default")
      (node (ref "D7") (pin "23") (pinfunction "~{INT}_23") (pintype "bidirectional"))
    )
    (net (code "179") (name "unconnected-(D8A-GPA1-Pad34)") (class "Default")
      (node (ref "D8") (pin "34") (pinfunction "GPA1_34") (pintype "bidirectional"))
    )
    (net (code "180") (name "unconnected-(D8A-HLGT-Pad32)") (class "Default")
      (node (ref "D8") (pin "32") (pinfunction "HLGT_32") (pintype "bidirectional"))
    )
    (net (code "181") (name "unconnected-(D8A-IRQ-Pad31)") (class "Default")
      (node (ref "D8") (pin "31") (pinfunction "IRQ_31") (pintype "bidirectional"))
    )
    (net (code "182") (name "unconnected-(D8A-LA0-Pad39)") (class "Default")
      (node (ref "D8") (pin "39") (pinfunction "LA0_39") (pintype "bidirectional"))
    )
    (net (code "183") (name "unconnected-(D8A-LA1-Pad38)") (class "Default")
      (node (ref "D8") (pin "38") (pinfunction "LA1_38") (pintype "bidirectional"))
    )
    (net (code "184") (name "unconnected-(D8A-LC3-Pad1)") (class "Default")
      (node (ref "D8") (pin "1") (pinfunction "LC3_1") (pintype "bidirectional"))
    )
    (net (code "185") (name "unconnected-(D8A-LPEN-Pad11)") (class "Default")
      (node (ref "D8") (pin "11") (pinfunction "LPEN_11") (pintype "bidirectional"))
    )
    (net (code "186") (name "unconnected-(D8A-RVV-Pad36)") (class "Default")
      (node (ref "D8") (pin "36") (pinfunction "RVV_36") (pintype "bidirectional"))
    )
    (net (code "187") (name "unconnected-(D10C-O-Pad8)") (class "Default")
      (node (ref "D10") (pin "8") (pinfunction "O_8") (pintype "output"))
    )
    (net (code "188") (name "unconnected-(D10D-O-Pad11)") (class "Default")
      (node (ref "D10") (pin "11") (pinfunction "O_11") (pintype "output"))
    )
    (net (code "189") (name "unconnected-(D11A-Y1-Pad14)") (class "Default")
      (node (ref "D11") (pin "14") (pinfunction "Y1_14") (pintype "output"))
    )
    (net (code "190") (name "unconnected-(D11A-Y3-Pad12)") (class "Default")
      (node (ref "D11") (pin "12") (pinfunction "Y3_12") (pintype "output"))
    )
    (net (code "191") (name "unconnected-(D11A-Y5-Pad10)") (class "Default")
      (node (ref "D11") (pin "10") (pinfunction "Y5_10") (pintype "output"))
    )
    (net (code "192") (name "unconnected-(D12A-D6-Pad16)") (class "Default")
      (node (ref "D12") (pin "16") (pinfunction "D6_16") (pintype "bidirectional"))
    )
    (net (code "193") (name "unconnected-(D12A-D7-Pad17)") (class "Default")
      (node (ref "D12") (pin "17") (pinfunction "D7_17") (pintype "bidirectional"))
    )
    (net (code "194") (name "unconnected-(D13A-~{Q}-Pad6)") (class "Default")
      (node (ref "D13") (pin "6") (pinfunction "~{Q}_6") (pintype "output"))
    )
    (net (code "195") (name "unconnected-(D13B-Q-Pad9)") (class "Default")
      (node (ref "D13") (pin "9") (pinfunction "Q_9") (pintype "output"))
    )
    (net (code "196") (name "unconnected-(D15A-QA-Pad4)") (class "Default")
      (node (ref "D15") (pin "4") (pinfunction "QA_4") (pintype "output"))
    )
    (net (code "197") (name "unconnected-(D15A-QB-Pad6)") (class "Default")
      (node (ref "D15") (pin "6") (pinfunction "QB_6") (pintype "output"))
    )
    (net (code "198") (name "unconnected-(D15A-QC-Pad8)") (class "Default")
      (node (ref "D15") (pin "8") (pinfunction "QC_8") (pintype "output"))
    )
    (net (code "199") (name "unconnected-(D15A-QD-Pad10)") (class "Default")
      (node (ref "D15") (pin "10") (pinfunction "QD_10") (pintype "output"))
    )
    (net (code "200") (name "unconnected-(D15A-QE-Pad14)") (class "Default")
      (node (ref "D15") (pin "14") (pinfunction "QE_14") (pintype "output"))
    )
    (net (code "201") (name "unconnected-(D15A-QG-Pad18)") (class "Default")
      (node (ref "D15") (pin "18") (pinfunction "QG_18") (pintype "output"))
    )
    (net (code "202") (name "unconnected-(D17-NC-Pad1)") (class "Default")
      (node (ref "D17") (pin "1") (pinfunction "NC_1") (pintype "no_connect"))
    )
    (net (code "203") (name "unconnected-(D17-NC-Pad26)") (class "Default")
      (node (ref "D17") (pin "26") (pinfunction "NC_26") (pintype "no_connect"))
    )
    (net (code "204") (name "unconnected-(DIN1A-2-PadP2)") (class "Default")
      (node (ref "DIN1") (pin "P2") (pinfunction "2_P2") (pintype "passive"))
    )
    (net (code "205") (name "unconnected-(DIN1A-6-PadP6)") (class "Default")
      (node (ref "DIN1") (pin "P6") (pinfunction "6_P6") (pintype "passive"))
    )
    (net (code "206") (name "unconnected-(R104-Pad2)") (class "Default")
      (node (ref "R104") (pin "2") (pinfunction "2_2") (pintype "passive"))
    )
    (net (code "207") (name "unconnected-(R104-Pad3)") (class "Default")
      (node (ref "R104") (pin "3") (pinfunction "3_3") (pintype "passive"))
    )
    (net (code "208") (name "~{CS_CCRT}") (class "Default")
      (node (ref "D11") (pin "11") (pinfunction "Y4_11") (pintype "output"))
      (node (ref "D8") (pin "22") (pinfunction "CS_22") (pintype "input"))
    )
    (net (code "209") (name "~{CS_D14}") (class "Default")
      (node (ref "D11") (pin "13") (pinfunction "Y2_13") (pintype "output"))
      (node (ref "D14") (pin "6") (pinfunction "CS_6") (pintype "input"))
    )
    (net (code "210") (name "~{CS_D20}") (class "Default")
      (node (ref "D11") (pin "15") (pinfunction "Y0_15") (pintype "output"))
      (node (ref "D20") (pin "6") (pinfunction "CS_6") (pintype "input"))
    )
    (net (code "211") (name "~{CS_DMA}") (class "Default")
      (node (ref "D11") (pin "9") (pinfunction "Y6_9") (pintype "output"))
      (node (ref "D2") (pin "11") (pinfunction "CS_11") (pintype "input"))
      (node (ref "D4") (pin "12") (pinfunction "I0_12") (pintype "input"))
    )
    (net (code "212") (name "~{CS_RAM}") (class "Default")
      (node (ref "D10") (pin "6") (pinfunction "O_6") (pintype "output"))
      (node (ref "D22") (pin "20") (pinfunction "~{CS}_20") (pintype "input"))
    )
    (net (code "213") (name "~{CS_ROM}") (class "Default")
      (node (ref "D17") (pin "20") (pinfunction "~{CE}_20") (pintype "input"))
      (node (ref "D4") (pin "8") (pinfunction "O_8") (pintype "output"))
    )
    (net (code "214") (name "~{FORCE_CS_ROM}") (class "Default")
      (node (ref "D10") (pin "5") (pinfunction "I1_5") (pintype "input"))
      (node (ref "D13") (pin "5") (pinfunction "Q_5") (pintype "output"))
      (node (ref "D4") (pin "9") (pinfunction "I0_9") (pintype "input"))
    )
    (net (code "215") (name "~{I{slash}OR}") (class "Default")
      (node (ref "D2") (pin "1") (pinfunction "~{I/OR}_1") (pintype "bidirectional"))
      (node (ref "D4") (pin "1") (pinfunction "I0_1") (pintype "input"))
      (node (ref "R4") (pin "4") (pinfunction "4_4") (pintype "passive"))
    )
    (net (code "216") (name "~{MEMW}") (class "Default")
      (node (ref "D2") (pin "4") (pinfunction "~{MEMW}_4") (pintype "bidirectional"))
      (node (ref "D5") (pin "2") (pinfunction "I1_2") (pintype "input"))
      (node (ref "R5") (pin "4") (pinfunction "4_4") (pintype "passive"))
    )
    (net (code "217") (name "~{RD}") (class "Default")
      (node (ref "D14") (pin "5") (pinfunction "RD_5") (pintype "input"))
      (node (ref "D17") (pin "22") (pinfunction "~{OE}_22") (pintype "input"))
      (node (ref "D20") (pin "5") (pinfunction "RD_5") (pintype "input"))
      (node (ref "D22") (pin "22") (pinfunction "~{OE}_22") (pintype "input"))
      (node (ref "D5") (pin "3") (pinfunction "O_3") (pintype "output"))
      (node (ref "D8") (pin "9") (pinfunction "RD_9") (pintype "input"))
    )
    (net (code "218") (name "~{RST}") (class "Default")
      (node (ref "C2") (pin "1") (pinfunction "1_1") (pintype "passive"))
      (node (ref "D1") (pin "2") (pinfunction "RESIN_2") (pintype "input"))
      (node (ref "EXT_RST") (pin "1") (pinfunction "1_1") (pintype "passive"))
      (node (ref "R1") (pin "1") (pinfunction "1_1") (pintype "passive"))
      (node (ref "RESET") (pin "1") (pinfunction "S_1") (pintype "passive"))
      (node (ref "RESET") (pin "2") (pinfunction "S1_2") (pintype "passive"))
      (node (ref "VD1") (pin "A") (pinfunction "A_A") (pintype "passive"))
      (node (ref "VD101") (pin "A") (pinfunction "A_A") (pintype "passive"))
    )
    (net (code "219") (name "~{VIDEO_SYNC}") (class "Default")
      (node (ref "D9") (pin "6") (pinfunction "O_6") (pintype "output"))
      (node (ref "R16") (pin "1") (pinfunction "1_1") (pintype "passive"))
    )
    (net (code "220") (name "~{WR}") (class "Default")
      (node (ref "D14") (pin "36") (pinfunction "WR_36") (pintype "input"))
      (node (ref "D2") (pin "2") (pinfunction "~{I/OW}_2") (pintype "bidirectional"))
      (node (ref "D20") (pin "36") (pinfunction "WR_36") (pintype "input"))
      (node (ref "D22") (pin "27") (pinfunction "~{WE}_27") (pintype "input"))
      (node (ref "D4") (pin "2") (pinfunction "I1_2") (pintype "input"))
      (node (ref "D6") (pin "18") (pinfunction "WR_18") (pintype "output"))
    )
  )
)
